# backplane_v3.net
KiCad netlist of a schematic drawn in EAGLE
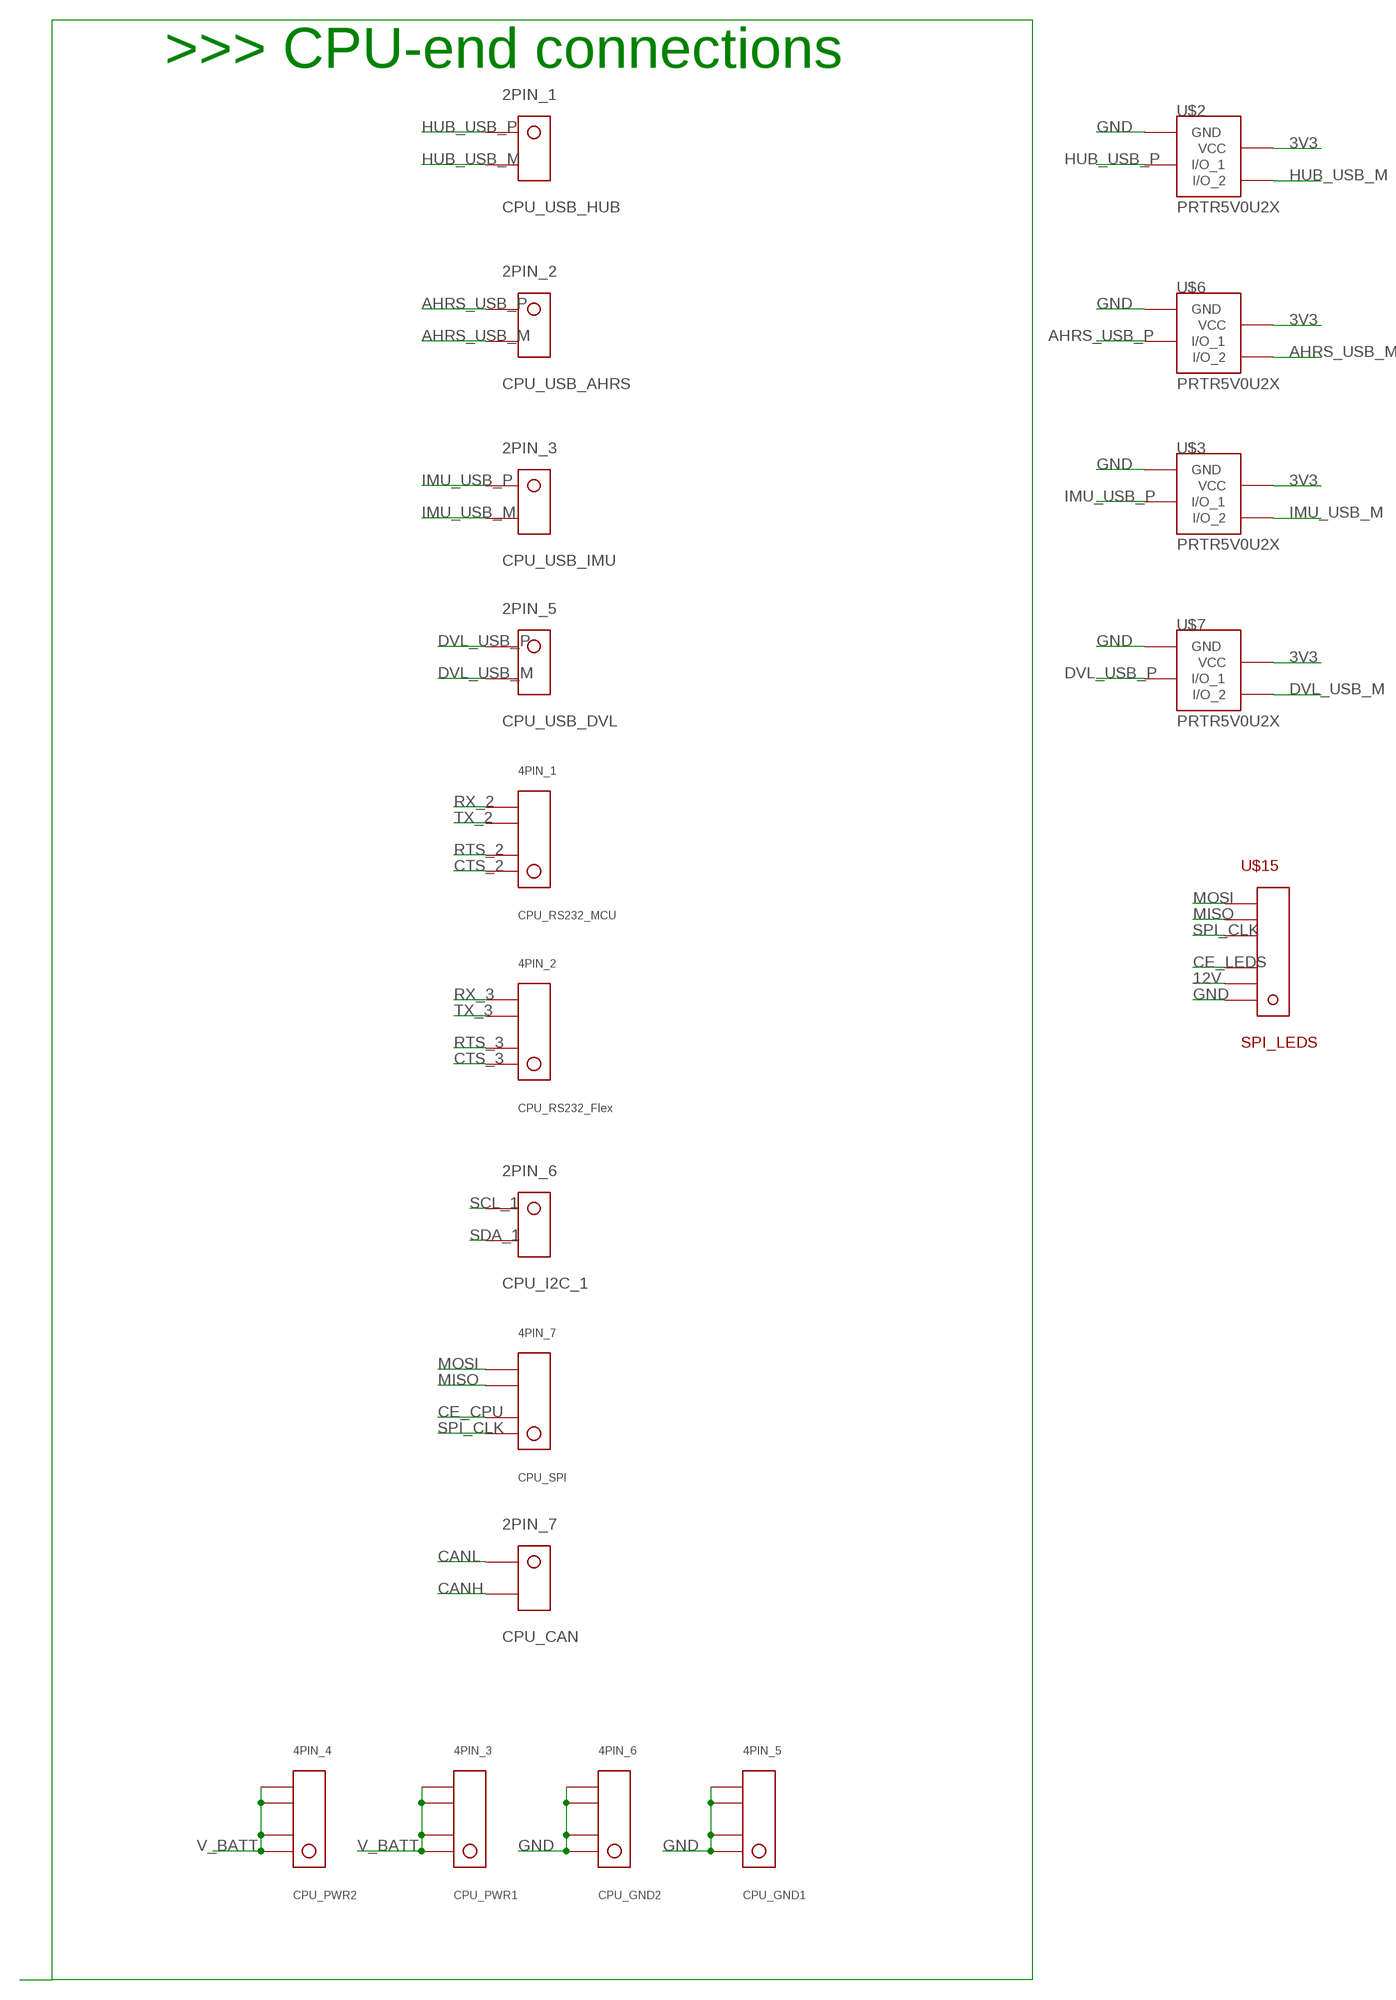
[diagram p0: schematic, sheet 1, part 1 of 3]
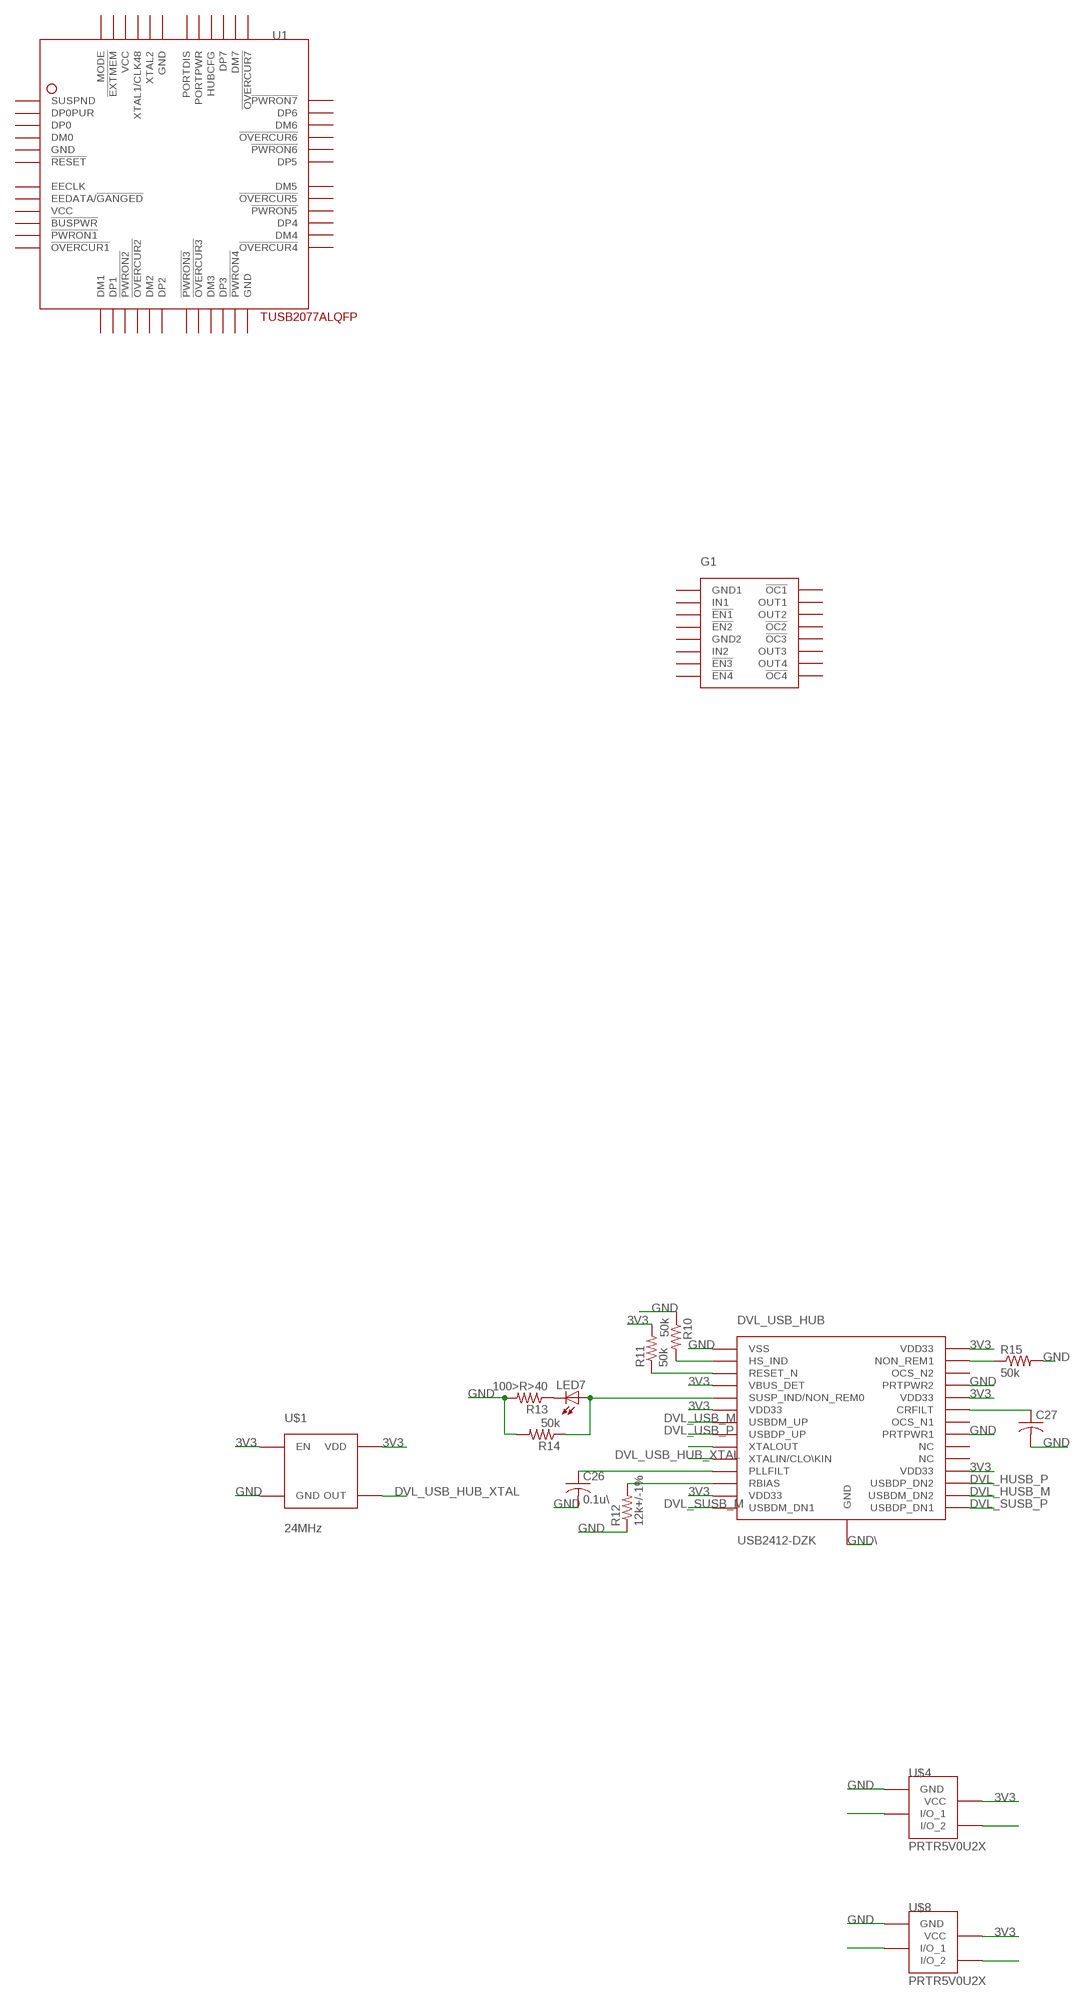
[diagram p1: schematic, sheet 1, part 2 of 3]
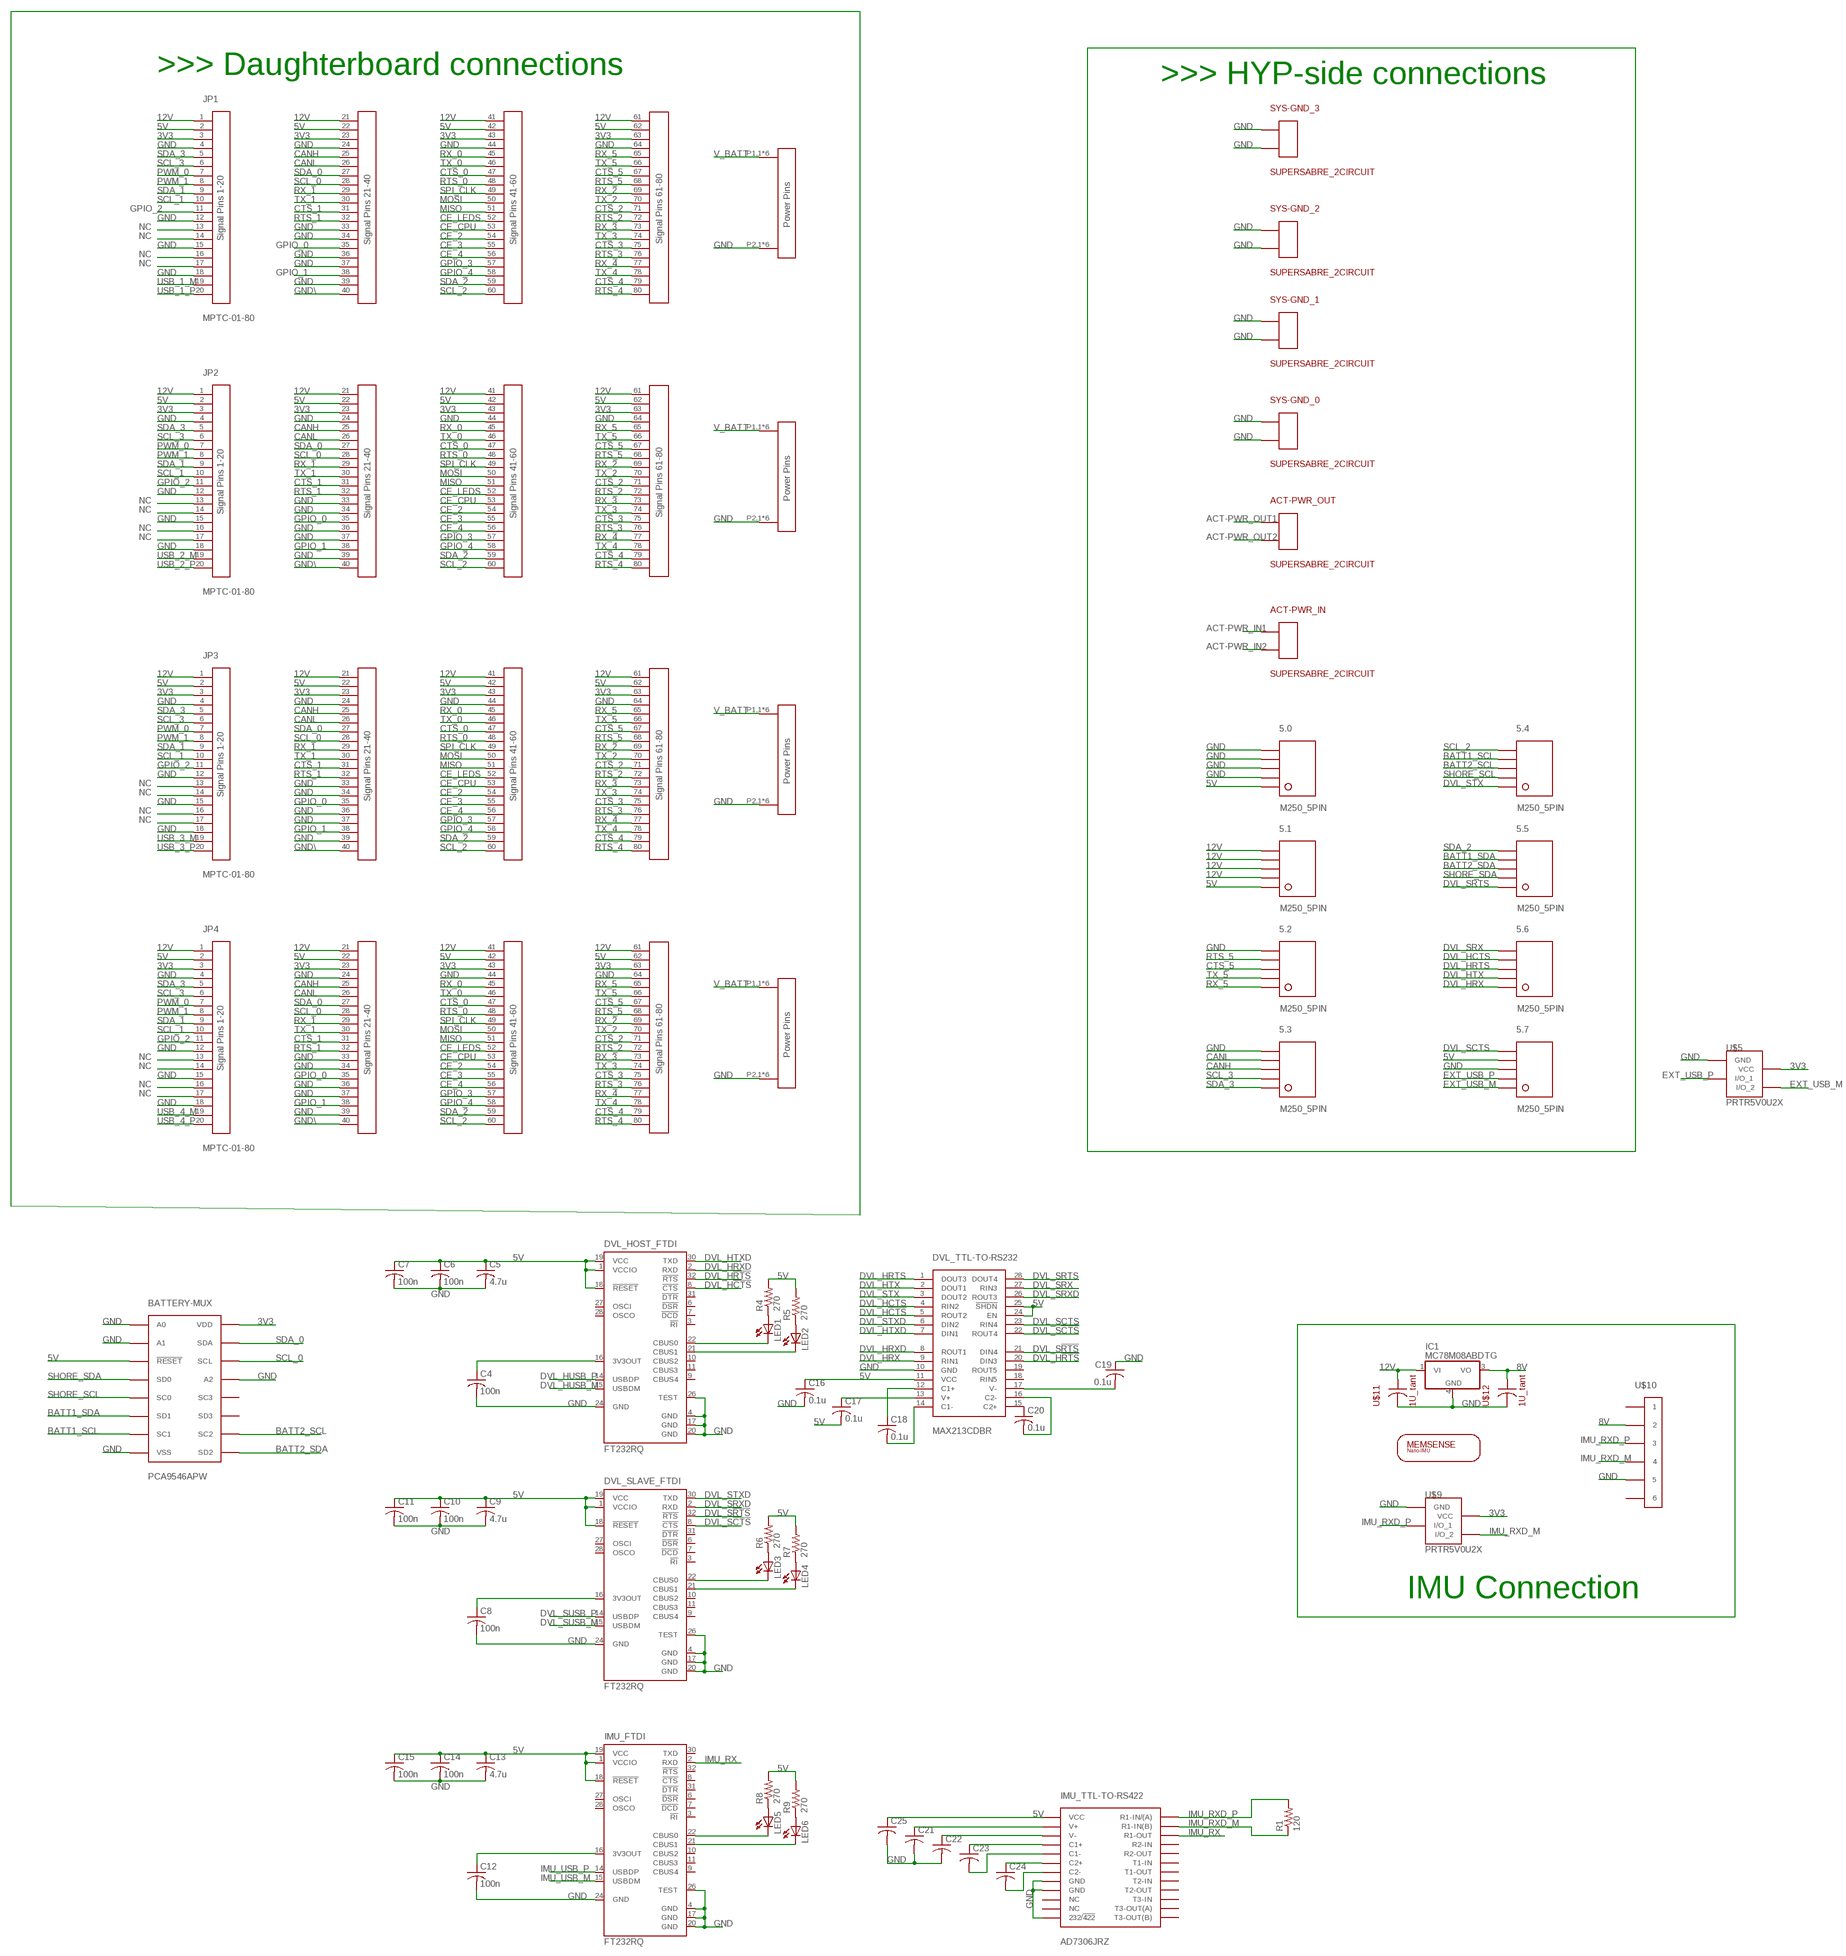
[diagram p2: schematic, sheet 1, part 3 of 3]

(export (version "E")
  (design (tool "Eeschema 10.0.6"))
  (components
    (comp (ref "2PIN_1")
      (value "CPU_USB_HUB")
      (footprint "eagle-import:KK254_VERT_2PIN")
      (libsource (lib "eagle-import") (part "KK254_VERT_2PIN22-29-2021"))
    )
    (comp (ref "2PIN_2")
      (value "CPU_USB_AHRS")
      (footprint "eagle-import:KK254_VERT_2PIN")
      (libsource (lib "eagle-import") (part "KK254_VERT_2PIN22-29-2021"))
    )
    (comp (ref "2PIN_3")
      (value "CPU_USB_IMU")
      (footprint "eagle-import:KK254_VERT_2PIN")
      (libsource (lib "eagle-import") (part "KK254_VERT_2PIN22-29-2021"))
    )
    (comp (ref "2PIN_5")
      (value "CPU_USB_DVL")
      (footprint "eagle-import:KK254_VERT_2PIN")
      (libsource (lib "eagle-import") (part "KK254_VERT_2PIN22-29-2021"))
    )
    (comp (ref "2PIN_6")
      (value "CPU_I2C_1")
      (footprint "eagle-import:KK254_VERT_2PIN")
      (libsource (lib "eagle-import") (part "KK254_VERT_2PIN22-29-2021"))
    )
    (comp (ref "2PIN_7")
      (value "CPU_CAN")
      (footprint "eagle-import:KK254_VERT_2PIN")
      (libsource (lib "eagle-import") (part "KK254_VERT_2PIN22-29-2021"))
    )
    (comp (ref "4PIN_1")
      (value "CPU_RS232_MCU")
      (footprint "eagle-import:KK254_VERT_4PIN")
      (libsource (lib "eagle-import") (part "KK254_VERT_4PIN22-29-2041"))
    )
    (comp (ref "4PIN_2")
      (value "CPU_RS232_Flex")
      (footprint "eagle-import:KK254_VERT_4PIN")
      (libsource (lib "eagle-import") (part "KK254_VERT_4PIN22-29-2041"))
    )
    (comp (ref "4PIN_3")
      (value "CPU_PWR1")
      (footprint "eagle-import:KK254_VERT_4PIN")
      (libsource (lib "eagle-import") (part "KK254_VERT_4PIN22-29-2041"))
    )
    (comp (ref "4PIN_4")
      (value "CPU_PWR2")
      (footprint "eagle-import:KK254_VERT_4PIN")
      (libsource (lib "eagle-import") (part "KK254_VERT_4PIN22-29-2041"))
    )
    (comp (ref "4PIN_5")
      (value "CPU_GND1")
      (footprint "eagle-import:KK254_VERT_4PIN")
      (libsource (lib "eagle-import") (part "KK254_VERT_4PIN22-29-2041"))
    )
    (comp (ref "4PIN_6")
      (value "CPU_GND2")
      (footprint "eagle-import:KK254_VERT_4PIN")
      (libsource (lib "eagle-import") (part "KK254_VERT_4PIN22-29-2041"))
    )
    (comp (ref "4PIN_7")
      (value "CPU_SPI")
      (footprint "eagle-import:KK254_VERT_4PIN")
      (libsource (lib "eagle-import") (part "KK254_VERT_4PIN22-29-2041"))
    )
    (comp (ref "5.0")
      (value "M250_5PIN")
      (footprint "eagle-import:M205_5PIN")
      (libsource (lib "eagle-import") (part "M250_5PIN"))
    )
    (comp (ref "5.1")
      (value "M250_5PIN")
      (footprint "eagle-import:M205_5PIN")
      (libsource (lib "eagle-import") (part "M250_5PIN"))
    )
    (comp (ref "5.2")
      (value "M250_5PIN")
      (footprint "eagle-import:M205_5PIN")
      (libsource (lib "eagle-import") (part "M250_5PIN"))
    )
    (comp (ref "5.3")
      (value "M250_5PIN")
      (footprint "eagle-import:M205_5PIN")
      (libsource (lib "eagle-import") (part "M250_5PIN"))
    )
    (comp (ref "5.4")
      (value "M250_5PIN")
      (footprint "eagle-import:M205_5PIN")
      (libsource (lib "eagle-import") (part "M250_5PIN"))
    )
    (comp (ref "5.5")
      (value "M250_5PIN")
      (footprint "eagle-import:M205_5PIN")
      (libsource (lib "eagle-import") (part "M250_5PIN"))
    )
    (comp (ref "5.6")
      (value "M250_5PIN")
      (footprint "eagle-import:M205_5PIN")
      (libsource (lib "eagle-import") (part "M250_5PIN"))
    )
    (comp (ref "5.7")
      (value "M250_5PIN")
      (footprint "eagle-import:M205_5PIN")
      (libsource (lib "eagle-import") (part "M250_5PIN"))
    )
    (comp (ref "ACT-PWR_IN")
      (value "SUPERSABRE_2CIRCUIT")
      (footprint "eagle-import:SUPERSABRE_2CIRCUIT")
      (libsource (lib "eagle-import") (part "SUPERSABRE_2CIRCUIT"))
    )
    (comp (ref "ACT-PWR_OUT")
      (value "SUPERSABRE_2CIRCUIT")
      (footprint "eagle-import:SUPERSABRE_2CIRCUIT")
      (libsource (lib "eagle-import") (part "SUPERSABRE_2CIRCUIT"))
    )
    (comp (ref "BATTERY-MUX")
      (value "PCA9546APW")
      (footprint "eagle-import:TSSOP16")
      (libsource (lib "eagle-import") (part "PCA9546APW"))
    )
    (comp (ref "C4")
      (value "100n")
      (footprint "eagle-import:C0805")
      (libsource (lib "eagle-import") (part "C-USC0805"))
    )
    (comp (ref "C5")
      (value "4.7u")
      (footprint "eagle-import:C0805")
      (libsource (lib "eagle-import") (part "C-USC0805"))
    )
    (comp (ref "C6")
      (value "100n")
      (footprint "eagle-import:C0805")
      (libsource (lib "eagle-import") (part "C-USC0805"))
    )
    (comp (ref "C7")
      (value "100n")
      (footprint "eagle-import:C0805")
      (libsource (lib "eagle-import") (part "C-USC0805"))
    )
    (comp (ref "C8")
      (value "100n")
      (footprint "eagle-import:C0805")
      (libsource (lib "eagle-import") (part "C-USC0805"))
    )
    (comp (ref "C9")
      (value "4.7u")
      (footprint "eagle-import:C0805")
      (libsource (lib "eagle-import") (part "C-USC0805"))
    )
    (comp (ref "C10")
      (value "100n")
      (footprint "eagle-import:C0805")
      (libsource (lib "eagle-import") (part "C-USC0805"))
    )
    (comp (ref "C11")
      (value "100n")
      (footprint "eagle-import:C0805")
      (libsource (lib "eagle-import") (part "C-USC0805"))
    )
    (comp (ref "C12")
      (value "100n")
      (footprint "eagle-import:C0805")
      (libsource (lib "eagle-import") (part "C-USC0805"))
    )
    (comp (ref "C13")
      (value "4.7u")
      (footprint "eagle-import:C0805")
      (libsource (lib "eagle-import") (part "C-USC0805"))
    )
    (comp (ref "C14")
      (value "100n")
      (footprint "eagle-import:C0805")
      (libsource (lib "eagle-import") (part "C-USC0805"))
    )
    (comp (ref "C15")
      (value "100n")
      (footprint "eagle-import:C0805")
      (libsource (lib "eagle-import") (part "C-USC0805"))
    )
    (comp (ref "C16")
      (value "0.1u")
      (footprint "eagle-import:C0805")
      (libsource (lib "eagle-import") (part "C-USC0805"))
    )
    (comp (ref "C17")
      (value "0.1u")
      (footprint "eagle-import:C0805")
      (libsource (lib "eagle-import") (part "C-USC0805"))
    )
    (comp (ref "C18")
      (value "0.1u")
      (footprint "eagle-import:C0805")
      (libsource (lib "eagle-import") (part "C-USC0805"))
    )
    (comp (ref "C19")
      (value "0.1u")
      (footprint "eagle-import:C0805")
      (libsource (lib "eagle-import") (part "C-USC0805"))
    )
    (comp (ref "C20")
      (value "0.1u")
      (footprint "eagle-import:C0805")
      (libsource (lib "eagle-import") (part "C-USC0805"))
    )
    (comp (ref "C21")
      (value "C-USC0805")
      (footprint "eagle-import:C0805")
      (libsource (lib "eagle-import") (part "C-USC0805"))
    )
    (comp (ref "C22")
      (value "C-USC0805")
      (footprint "eagle-import:C0805")
      (libsource (lib "eagle-import") (part "C-USC0805"))
    )
    (comp (ref "C23")
      (value "C-USC0805")
      (footprint "eagle-import:C0805")
      (libsource (lib "eagle-import") (part "C-USC0805"))
    )
    (comp (ref "C24")
      (value "C-USC0805")
      (footprint "eagle-import:C0805")
      (libsource (lib "eagle-import") (part "C-USC0805"))
    )
    (comp (ref "C25")
      (value "C-USC0805")
      (footprint "eagle-import:C0805")
      (libsource (lib "eagle-import") (part "C-USC0805"))
    )
    (comp (ref "C26")
      (value "0.1u\\")
      (footprint "eagle-import:C0805")
      (libsource (lib "eagle-import") (part "C-USC0805"))
    )
    (comp (ref "C27")
      (value "C-USC0805")
      (footprint "eagle-import:C0805")
      (libsource (lib "eagle-import") (part "C-USC0805"))
    )
    (comp (ref "DVL_HOST_FTDI")
      (value "FT232RQ")
      (footprint "eagle-import:QFN32")
      (libsource (lib "eagle-import") (part "FT232RQ"))
    )
    (comp (ref "DVL_SLAVE_FTDI")
      (value "FT232RQ")
      (footprint "eagle-import:QFN32")
      (libsource (lib "eagle-import") (part "FT232RQ"))
    )
    (comp (ref "DVL_TTL-TO-RS232")
      (value "MAX213CDBR")
      (footprint "eagle-import:SSOP28DB")
      (libsource (lib "eagle-import") (part "MAX213CDBR"))
    )
    (comp (ref "DVL_USB_HUB")
      (value "USB2412-DZK")
      (footprint "eagle-import:QFN-28")
      (libsource (lib "eagle-import") (part "USB2412-DZK"))
    )
    (comp (ref "G1")
      (value "TPS2044BBD-SOIC")
      (footprint "eagle-import:TPS2044")
      (libsource (lib "eagle-import") (part "TPS2044BBD-SOIC"))
    )
    (comp (ref "IC1")
      (value "MC78M08ABDTG")
      (footprint "eagle-import:DPACK_3")
      (libsource (lib "eagle-import") (part "MC78M08ABDTG"))
    )
    (comp (ref "IMU_FTDI")
      (value "FT232RQ")
      (footprint "eagle-import:QFN32")
      (libsource (lib "eagle-import") (part "FT232RQ"))
    )
    (comp (ref "IMU_TTL-TO-RS422")
      (value "AD7306JRZ")
      (footprint "eagle-import:SOIC-24")
      (libsource (lib "eagle-import") (part "AD7306JRZ"))
    )
    (comp (ref "JP1")
      (value "MPTC-01-80")
      (footprint "eagle-import:MPTC-01-80")
      (libsource (lib "eagle-import") (part "MPTC-01-80"))
    )
    (comp (ref "JP2")
      (value "MPTC-01-80")
      (footprint "eagle-import:MPTC-01-80")
      (libsource (lib "eagle-import") (part "MPTC-01-80"))
    )
    (comp (ref "JP3")
      (value "MPTC-01-80")
      (footprint "eagle-import:MPTC-01-80")
      (libsource (lib "eagle-import") (part "MPTC-01-80"))
    )
    (comp (ref "JP4")
      (value "MPTC-01-80")
      (footprint "eagle-import:MPTC-01-80")
      (libsource (lib "eagle-import") (part "MPTC-01-80"))
    )
    (comp (ref "LED1")
      (value "LEDCHIPLED_0805")
      (footprint "eagle-import:CHIPLED_0805")
      (libsource (lib "eagle-import") (part "LEDCHIPLED_0805"))
    )
    (comp (ref "LED2")
      (value "LEDCHIPLED_0805")
      (footprint "eagle-import:CHIPLED_0805")
      (libsource (lib "eagle-import") (part "LEDCHIPLED_0805"))
    )
    (comp (ref "LED3")
      (value "LEDCHIPLED_0805")
      (footprint "eagle-import:CHIPLED_0805")
      (libsource (lib "eagle-import") (part "LEDCHIPLED_0805"))
    )
    (comp (ref "LED4")
      (value "LEDCHIPLED_0805")
      (footprint "eagle-import:CHIPLED_0805")
      (libsource (lib "eagle-import") (part "LEDCHIPLED_0805"))
    )
    (comp (ref "LED5")
      (value "LEDCHIPLED_0805")
      (footprint "eagle-import:CHIPLED_0805")
      (libsource (lib "eagle-import") (part "LEDCHIPLED_0805"))
    )
    (comp (ref "LED6")
      (value "LEDCHIPLED_0805")
      (footprint "eagle-import:CHIPLED_0805")
      (libsource (lib "eagle-import") (part "LEDCHIPLED_0805"))
    )
    (comp (ref "LED7")
      (value "LEDCHIPLED_0805")
      (footprint "eagle-import:CHIPLED_0805")
      (libsource (lib "eagle-import") (part "LEDCHIPLED_0805"))
    )
    (comp (ref "R1")
      (value "120")
      (footprint "eagle-import:R0805")
      (libsource (lib "eagle-import") (part "R-US_R0805"))
    )
    (comp (ref "R4")
      (value "270")
      (footprint "eagle-import:R0805")
      (libsource (lib "eagle-import") (part "R-US_R0805"))
    )
    (comp (ref "R5")
      (value "270")
      (footprint "eagle-import:R0805")
      (libsource (lib "eagle-import") (part "R-US_R0805"))
    )
    (comp (ref "R6")
      (value "270")
      (footprint "eagle-import:R0805")
      (libsource (lib "eagle-import") (part "R-US_R0805"))
    )
    (comp (ref "R7")
      (value "270")
      (footprint "eagle-import:R0805")
      (libsource (lib "eagle-import") (part "R-US_R0805"))
    )
    (comp (ref "R8")
      (value "270")
      (footprint "eagle-import:R0805")
      (libsource (lib "eagle-import") (part "R-US_R0805"))
    )
    (comp (ref "R9")
      (value "270")
      (footprint "eagle-import:R0805")
      (libsource (lib "eagle-import") (part "R-US_R0805"))
    )
    (comp (ref "R10")
      (value "50k")
      (footprint "eagle-import:R0805")
      (libsource (lib "eagle-import") (part "R-US_R0805"))
    )
    (comp (ref "R11")
      (value "50k")
      (footprint "eagle-import:R0805")
      (libsource (lib "eagle-import") (part "R-US_R0805"))
    )
    (comp (ref "R12")
      (value "12k+/-1%")
      (footprint "eagle-import:R0805")
      (libsource (lib "eagle-import") (part "R-US_R0805"))
    )
    (comp (ref "R13")
      (value "100>R>40")
      (footprint "eagle-import:R0805")
      (libsource (lib "eagle-import") (part "R-US_R0805"))
    )
    (comp (ref "R14")
      (value "50k")
      (footprint "eagle-import:R0805")
      (libsource (lib "eagle-import") (part "R-US_R0805"))
    )
    (comp (ref "R15")
      (value "50k")
      (footprint "eagle-import:R0805")
      (libsource (lib "eagle-import") (part "R-US_R0805"))
    )
    (comp (ref "SYS-GND_0")
      (value "SUPERSABRE_2CIRCUIT")
      (footprint "eagle-import:SUPERSABRE_2CIRCUIT")
      (libsource (lib "eagle-import") (part "SUPERSABRE_2CIRCUIT"))
    )
    (comp (ref "SYS-GND_1")
      (value "SUPERSABRE_2CIRCUIT")
      (footprint "eagle-import:SUPERSABRE_2CIRCUIT")
      (libsource (lib "eagle-import") (part "SUPERSABRE_2CIRCUIT"))
    )
    (comp (ref "SYS-GND_2")
      (value "SUPERSABRE_2CIRCUIT")
      (footprint "eagle-import:SUPERSABRE_2CIRCUIT")
      (libsource (lib "eagle-import") (part "SUPERSABRE_2CIRCUIT"))
    )
    (comp (ref "SYS-GND_3")
      (value "SUPERSABRE_2CIRCUIT")
      (footprint "eagle-import:SUPERSABRE_2CIRCUIT")
      (libsource (lib "eagle-import") (part "SUPERSABRE_2CIRCUIT"))
    )
    (comp (ref "U$1")
      (value "24MHz")
      (footprint "eagle-import:4-CDFN_3.2X2.5MM")
      (libsource (lib "eagle-import") (part "DCS6XXX"))
    )
    (comp (ref "U$2")
      (value "PRTR5V0U2X")
      (footprint "eagle-import:SOT143B")
      (libsource (lib "eagle-import") (part "PRTR5V0U2X"))
    )
    (comp (ref "U$3")
      (value "PRTR5V0U2X")
      (footprint "eagle-import:SOT143B")
      (libsource (lib "eagle-import") (part "PRTR5V0U2X"))
    )
    (comp (ref "U$4")
      (value "PRTR5V0U2X")
      (footprint "eagle-import:SOT143B")
      (libsource (lib "eagle-import") (part "PRTR5V0U2X"))
    )
    (comp (ref "U$5")
      (value "PRTR5V0U2X")
      (footprint "eagle-import:SOT143B")
      (libsource (lib "eagle-import") (part "PRTR5V0U2X"))
    )
    (comp (ref "U$6")
      (value "PRTR5V0U2X")
      (footprint "eagle-import:SOT143B")
      (libsource (lib "eagle-import") (part "PRTR5V0U2X"))
    )
    (comp (ref "U$7")
      (value "PRTR5V0U2X")
      (footprint "eagle-import:SOT143B")
      (libsource (lib "eagle-import") (part "PRTR5V0U2X"))
    )
    (comp (ref "U$8")
      (value "PRTR5V0U2X")
      (footprint "eagle-import:SOT143B")
      (libsource (lib "eagle-import") (part "PRTR5V0U2X"))
    )
    (comp (ref "U$9")
      (value "PRTR5V0U2X")
      (footprint "eagle-import:SOT143B")
      (libsource (lib "eagle-import") (part "PRTR5V0U2X"))
    )
    (comp (ref "U$10")
      (value "HR30-6R-6PD")
      (footprint "eagle-import:HR30-6R-6PD")
      (libsource (lib "eagle-import") (part "HR30-6R-6PD"))
    )
    (comp (ref "U$11")
      (value "1U_tant")
      (footprint "eagle-import:F93-XX-XXX-X-A")
      (libsource (lib "eagle-import") (part "F93-XX-XXX-X-A"))
    )
    (comp (ref "U$12")
      (value "1U_tant")
      (footprint "eagle-import:F93-XX-XXX-X-A")
      (libsource (lib "eagle-import") (part "F93-XX-XXX-X-A"))
    )
    (comp (ref "U$13")
      (value "MEMSENSE_NIMU")
      (footprint "eagle-import:MEMSENSE_NIMU")
      (libsource (lib "eagle-import") (part "MEMSENSE_NIMU"))
    )
    (comp (ref "U$15")
      (value "SPI_LEDS")
      (footprint "eagle-import:KK254_6PIN")
      (libsource (lib "eagle-import") (part "KK254_6PIN"))
    )
    (comp (ref "U1")
      (value "TUSB2077ALQFP")
      (footprint "eagle-import:48-LQFP_0.5MM_PITCH")
      (libsource (lib "eagle-import") (part "TUSB2077ALQFP"))
    )
  )
  (nets
    (net (code "1") (name "/3V3") (class "Default")
      (node (ref "BATTERY-MUX") (pin "P$16") (pinfunction "VDD_P$16") (pintype "bidirectional"))
      (node (ref "DVL_USB_HUB") (pin "P$10") (pinfunction "VDD33_P$10") (pintype "bidirectional"))
      (node (ref "DVL_USB_HUB") (pin "P$14") (pinfunction "VDD33_P$14") (pintype "bidirectional"))
      (node (ref "DVL_USB_HUB") (pin "P$18") (pinfunction "VBUS_DET_P$18") (pintype "bidirectional"))
      (node (ref "DVL_USB_HUB") (pin "P$20") (pinfunction "VDD33_P$20") (pintype "bidirectional"))
      (node (ref "DVL_USB_HUB") (pin "P$27") (pinfunction "VDD33_P$27") (pintype "bidirectional"))
      (node (ref "DVL_USB_HUB") (pin "P$4") (pinfunction "VDD33_P$4") (pintype "bidirectional"))
      (node (ref "JP1") (pin "23") (pinfunction "P$23_23") (pintype "bidirectional"))
      (node (ref "JP1") (pin "3") (pinfunction "P$3_3") (pintype "bidirectional"))
      (node (ref "JP1") (pin "43") (pinfunction "P$43_43") (pintype "bidirectional"))
      (node (ref "JP1") (pin "63") (pinfunction "P$63_63") (pintype "bidirectional"))
      (node (ref "JP2") (pin "23") (pinfunction "P$23_23") (pintype "bidirectional"))
      (node (ref "JP2") (pin "3") (pinfunction "P$3_3") (pintype "bidirectional"))
      (node (ref "JP2") (pin "43") (pinfunction "P$43_43") (pintype "bidirectional"))
      (node (ref "JP2") (pin "63") (pinfunction "P$63_63") (pintype "bidirectional"))
      (node (ref "JP3") (pin "23") (pinfunction "P$23_23") (pintype "bidirectional"))
      (node (ref "JP3") (pin "3") (pinfunction "P$3_3") (pintype "bidirectional"))
      (node (ref "JP3") (pin "43") (pinfunction "P$43_43") (pintype "bidirectional"))
      (node (ref "JP3") (pin "63") (pinfunction "P$63_63") (pintype "bidirectional"))
      (node (ref "JP4") (pin "23") (pinfunction "P$23_23") (pintype "bidirectional"))
      (node (ref "JP4") (pin "3") (pinfunction "P$3_3") (pintype "bidirectional"))
      (node (ref "JP4") (pin "43") (pinfunction "P$43_43") (pintype "bidirectional"))
      (node (ref "JP4") (pin "63") (pinfunction "P$63_63") (pintype "bidirectional"))
      (node (ref "R11") (pin "2") (pinfunction "2_2") (pintype "passive"))
      (node (ref "U$1") (pin "P$1") (pinfunction "EN_P$1") (pintype "bidirectional"))
      (node (ref "U$1") (pin "P$4") (pinfunction "VDD_P$4") (pintype "bidirectional"))
      (node (ref "U$2") (pin "P$4") (pinfunction "VCC_P$4") (pintype "bidirectional"))
      (node (ref "U$3") (pin "P$4") (pinfunction "VCC_P$4") (pintype "bidirectional"))
      (node (ref "U$4") (pin "P$4") (pinfunction "VCC_P$4") (pintype "bidirectional"))
      (node (ref "U$5") (pin "P$4") (pinfunction "VCC_P$4") (pintype "bidirectional"))
      (node (ref "U$6") (pin "P$4") (pinfunction "VCC_P$4") (pintype "bidirectional"))
      (node (ref "U$7") (pin "P$4") (pinfunction "VCC_P$4") (pintype "bidirectional"))
      (node (ref "U$8") (pin "P$4") (pinfunction "VCC_P$4") (pintype "bidirectional"))
      (node (ref "U$9") (pin "P$4") (pinfunction "VCC_P$4") (pintype "bidirectional"))
    )
    (net (code "2") (name "/5V") (class "Default")
      (node (ref "5.0") (pin "P$1") (pinfunction "P$1_P$1") (pintype "bidirectional"))
      (node (ref "5.0") (pin "P$2") (pinfunction "P$1_P$2") (pintype "bidirectional"))
      (node (ref "5.1") (pin "P$1") (pinfunction "P$1_P$1") (pintype "bidirectional"))
      (node (ref "5.1") (pin "P$2") (pinfunction "P$1_P$2") (pintype "bidirectional"))
      (node (ref "5.7") (pin "P$7") (pinfunction "P$4_P$7") (pintype "bidirectional"))
      (node (ref "5.7") (pin "P$8") (pinfunction "P$4_P$8") (pintype "bidirectional"))
      (node (ref "BATTERY-MUX") (pin "P$3") (pinfunction "~{RESET}_P$3") (pintype "bidirectional"))
      (node (ref "C10") (pin "1") (pinfunction "1_1") (pintype "passive"))
      (node (ref "C11") (pin "1") (pinfunction "1_1") (pintype "passive"))
      (node (ref "C13") (pin "1") (pinfunction "1_1") (pintype "passive"))
      (node (ref "C14") (pin "1") (pinfunction "1_1") (pintype "passive"))
      (node (ref "C15") (pin "1") (pinfunction "1_1") (pintype "passive"))
      (node (ref "C16") (pin "1") (pinfunction "1_1") (pintype "passive"))
      (node (ref "C17") (pin "2") (pinfunction "2_2") (pintype "passive"))
      (node (ref "C25") (pin "1") (pinfunction "1_1") (pintype "passive"))
      (node (ref "C5") (pin "1") (pinfunction "1_1") (pintype "passive"))
      (node (ref "C6") (pin "1") (pinfunction "1_1") (pintype "passive"))
      (node (ref "C7") (pin "1") (pinfunction "1_1") (pintype "passive"))
      (node (ref "C9") (pin "1") (pinfunction "1_1") (pintype "passive"))
      (node (ref "DVL_HOST_FTDI") (pin "1") (pinfunction "VCCIO_1") (pintype "power_in"))
      (node (ref "DVL_HOST_FTDI") (pin "18") (pinfunction "~{RESET}_18") (pintype "input"))
      (node (ref "DVL_HOST_FTDI") (pin "19") (pinfunction "VCC_19") (pintype "power_in"))
      (node (ref "DVL_SLAVE_FTDI") (pin "1") (pinfunction "VCCIO_1") (pintype "power_in"))
      (node (ref "DVL_SLAVE_FTDI") (pin "18") (pinfunction "~{RESET}_18") (pintype "input"))
      (node (ref "DVL_SLAVE_FTDI") (pin "19") (pinfunction "VCC_19") (pintype "power_in"))
      (node (ref "DVL_TTL-TO-RS232") (pin "11") (pinfunction "VCC_11") (pintype "bidirectional"))
      (node (ref "DVL_TTL-TO-RS232") (pin "24") (pinfunction "EN_24") (pintype "bidirectional"))
      (node (ref "DVL_TTL-TO-RS232") (pin "25") (pinfunction "~{SHDN}_25") (pintype "bidirectional"))
      (node (ref "IMU_FTDI") (pin "1") (pinfunction "VCCIO_1") (pintype "power_in"))
      (node (ref "IMU_FTDI") (pin "18") (pinfunction "~{RESET}_18") (pintype "input"))
      (node (ref "IMU_FTDI") (pin "19") (pinfunction "VCC_19") (pintype "power_in"))
      (node (ref "IMU_TTL-TO-RS422") (pin "P$7") (pinfunction "VCC_P$7") (pintype "bidirectional"))
      (node (ref "JP1") (pin "2") (pinfunction "P$2_2") (pintype "bidirectional"))
      (node (ref "JP1") (pin "22") (pinfunction "P$22_22") (pintype "bidirectional"))
      (node (ref "JP1") (pin "42") (pinfunction "P$42_42") (pintype "bidirectional"))
      (node (ref "JP1") (pin "62") (pinfunction "P$62_62") (pintype "bidirectional"))
      (node (ref "JP2") (pin "2") (pinfunction "P$2_2") (pintype "bidirectional"))
      (node (ref "JP2") (pin "22") (pinfunction "P$22_22") (pintype "bidirectional"))
      (node (ref "JP2") (pin "42") (pinfunction "P$42_42") (pintype "bidirectional"))
      (node (ref "JP2") (pin "62") (pinfunction "P$62_62") (pintype "bidirectional"))
      (node (ref "JP3") (pin "2") (pinfunction "P$2_2") (pintype "bidirectional"))
      (node (ref "JP3") (pin "22") (pinfunction "P$22_22") (pintype "bidirectional"))
      (node (ref "JP3") (pin "42") (pinfunction "P$42_42") (pintype "bidirectional"))
      (node (ref "JP3") (pin "62") (pinfunction "P$62_62") (pintype "bidirectional"))
      (node (ref "JP4") (pin "2") (pinfunction "P$2_2") (pintype "bidirectional"))
      (node (ref "JP4") (pin "22") (pinfunction "P$22_22") (pintype "bidirectional"))
      (node (ref "JP4") (pin "42") (pinfunction "P$42_42") (pintype "bidirectional"))
      (node (ref "JP4") (pin "62") (pinfunction "P$62_62") (pintype "bidirectional"))
      (node (ref "R4") (pin "2") (pinfunction "2_2") (pintype "passive"))
      (node (ref "R5") (pin "2") (pinfunction "2_2") (pintype "passive"))
      (node (ref "R6") (pin "2") (pinfunction "2_2") (pintype "passive"))
      (node (ref "R7") (pin "2") (pinfunction "2_2") (pintype "passive"))
      (node (ref "R8") (pin "2") (pinfunction "2_2") (pintype "passive"))
      (node (ref "R9") (pin "2") (pinfunction "2_2") (pintype "passive"))
    )
    (net (code "3") (name "/8V") (class "Default")
      (node (ref "IC1") (pin "3") (pinfunction "VO_3") (pintype "passive"))
      (node (ref "U$10") (pin "P$2") (pinfunction "2_P$2") (pintype "bidirectional"))
      (node (ref "U$12") (pin "P$1") (pinfunction "+_P$1") (pintype "bidirectional"))
    )
    (net (code "4") (name "/12V") (class "Default")
      (node (ref "5.1") (pin "P$10") (pinfunction "P$5_P$10") (pintype "bidirectional"))
      (node (ref "5.1") (pin "P$3") (pinfunction "P$2_P$3") (pintype "bidirectional"))
      (node (ref "5.1") (pin "P$4") (pinfunction "P$2_P$4") (pintype "bidirectional"))
      (node (ref "5.1") (pin "P$5") (pinfunction "P$3_P$5") (pintype "bidirectional"))
      (node (ref "5.1") (pin "P$6") (pinfunction "P$3_P$6") (pintype "bidirectional"))
      (node (ref "5.1") (pin "P$7") (pinfunction "P$4_P$7") (pintype "bidirectional"))
      (node (ref "5.1") (pin "P$8") (pinfunction "P$4_P$8") (pintype "bidirectional"))
      (node (ref "5.1") (pin "P$9") (pinfunction "P$5_P$9") (pintype "bidirectional"))
      (node (ref "IC1") (pin "1") (pinfunction "VI_1") (pintype "input"))
      (node (ref "JP1") (pin "1") (pinfunction "P$1_1") (pintype "bidirectional"))
      (node (ref "JP1") (pin "21") (pinfunction "P$21_21") (pintype "bidirectional"))
      (node (ref "JP1") (pin "41") (pinfunction "P$41_41") (pintype "bidirectional"))
      (node (ref "JP1") (pin "61") (pinfunction "P$61_61") (pintype "bidirectional"))
      (node (ref "JP2") (pin "1") (pinfunction "P$1_1") (pintype "bidirectional"))
      (node (ref "JP2") (pin "21") (pinfunction "P$21_21") (pintype "bidirectional"))
      (node (ref "JP2") (pin "41") (pinfunction "P$41_41") (pintype "bidirectional"))
      (node (ref "JP2") (pin "61") (pinfunction "P$61_61") (pintype "bidirectional"))
      (node (ref "JP3") (pin "1") (pinfunction "P$1_1") (pintype "bidirectional"))
      (node (ref "JP3") (pin "21") (pinfunction "P$21_21") (pintype "bidirectional"))
      (node (ref "JP3") (pin "41") (pinfunction "P$41_41") (pintype "bidirectional"))
      (node (ref "JP3") (pin "61") (pinfunction "P$61_61") (pintype "bidirectional"))
      (node (ref "JP4") (pin "1") (pinfunction "P$1_1") (pintype "bidirectional"))
      (node (ref "JP4") (pin "21") (pinfunction "P$21_21") (pintype "bidirectional"))
      (node (ref "JP4") (pin "41") (pinfunction "P$41_41") (pintype "bidirectional"))
      (node (ref "JP4") (pin "61") (pinfunction "P$61_61") (pintype "bidirectional"))
      (node (ref "U$11") (pin "P$1") (pinfunction "+_P$1") (pintype "bidirectional"))
      (node (ref "U$15") (pin "P$2") (pinfunction "P$2_P$2") (pintype "bidirectional"))
    )
    (net (code "5") (name "/ACT-PWR_IN1") (class "Default")
      (node (ref "ACT-PWR_IN") (pin "P$1") (pinfunction "P$1_P$1") (pintype "bidirectional"))
    )
    (net (code "6") (name "/ACT-PWR_IN2") (class "Default")
      (node (ref "ACT-PWR_IN") (pin "P$2") (pinfunction "P$2_P$2") (pintype "bidirectional"))
    )
    (net (code "7") (name "/ACT-PWR_OUT1") (class "Default")
      (node (ref "ACT-PWR_OUT") (pin "P$1") (pinfunction "P$1_P$1") (pintype "bidirectional"))
    )
    (net (code "8") (name "/ACT-PWR_OUT2") (class "Default")
      (node (ref "ACT-PWR_OUT") (pin "P$2") (pinfunction "P$2_P$2") (pintype "bidirectional"))
    )
    (net (code "9") (name "/AHRS_USB_M") (class "Default")
      (node (ref "2PIN_2") (pin "P$2") (pinfunction "P$2_P$2") (pintype "bidirectional"))
      (node (ref "U$6") (pin "P$3") (pinfunction "I/O_2_P$3") (pintype "bidirectional"))
    )
    (net (code "10") (name "/AHRS_USB_P") (class "Default")
      (node (ref "2PIN_2") (pin "P$1") (pinfunction "P$1_P$1") (pintype "bidirectional"))
      (node (ref "U$6") (pin "P$2") (pinfunction "I/O_1_P$2") (pintype "bidirectional"))
    )
    (net (code "11") (name "/BATT1_SCL") (class "Default")
      (node (ref "5.4") (pin "P$7") (pinfunction "P$4_P$7") (pintype "bidirectional"))
      (node (ref "5.4") (pin "P$8") (pinfunction "P$4_P$8") (pintype "bidirectional"))
      (node (ref "BATTERY-MUX") (pin "P$7") (pinfunction "SC1_P$7") (pintype "bidirectional"))
    )
    (net (code "12") (name "/BATT1_SDA") (class "Default")
      (node (ref "5.5") (pin "P$7") (pinfunction "P$4_P$7") (pintype "bidirectional"))
      (node (ref "5.5") (pin "P$8") (pinfunction "P$4_P$8") (pintype "bidirectional"))
      (node (ref "BATTERY-MUX") (pin "P$6") (pinfunction "SD1_P$6") (pintype "bidirectional"))
    )
    (net (code "13") (name "/BATT2_SCL") (class "Default")
      (node (ref "5.4") (pin "P$5") (pinfunction "P$3_P$5") (pintype "bidirectional"))
      (node (ref "5.4") (pin "P$6") (pinfunction "P$3_P$6") (pintype "bidirectional"))
      (node (ref "BATTERY-MUX") (pin "P$10") (pinfunction "SC2_P$10") (pintype "bidirectional"))
    )
    (net (code "14") (name "/BATT2_SDA") (class "Default")
      (node (ref "5.5") (pin "P$5") (pinfunction "P$3_P$5") (pintype "bidirectional"))
      (node (ref "5.5") (pin "P$6") (pinfunction "P$3_P$6") (pintype "bidirectional"))
      (node (ref "BATTERY-MUX") (pin "P$9") (pinfunction "SD2_P$9") (pintype "bidirectional"))
    )
    (net (code "15") (name "/CANH") (class "Default")
      (node (ref "2PIN_7") (pin "P$2") (pinfunction "P$2_P$2") (pintype "bidirectional"))
      (node (ref "5.3") (pin "P$5") (pinfunction "P$3_P$5") (pintype "bidirectional"))
      (node (ref "5.3") (pin "P$6") (pinfunction "P$3_P$6") (pintype "bidirectional"))
      (node (ref "JP1") (pin "25") (pinfunction "P$25_25") (pintype "bidirectional"))
      (node (ref "JP2") (pin "25") (pinfunction "P$25_25") (pintype "bidirectional"))
      (node (ref "JP3") (pin "25") (pinfunction "P$25_25") (pintype "bidirectional"))
      (node (ref "JP4") (pin "25") (pinfunction "P$25_25") (pintype "bidirectional"))
    )
    (net (code "16") (name "/CANL") (class "Default")
      (node (ref "2PIN_7") (pin "P$1") (pinfunction "P$1_P$1") (pintype "bidirectional"))
      (node (ref "5.3") (pin "P$7") (pinfunction "P$4_P$7") (pintype "bidirectional"))
      (node (ref "5.3") (pin "P$8") (pinfunction "P$4_P$8") (pintype "bidirectional"))
      (node (ref "JP1") (pin "26") (pinfunction "P$26_26") (pintype "bidirectional"))
      (node (ref "JP2") (pin "26") (pinfunction "P$26_26") (pintype "bidirectional"))
      (node (ref "JP3") (pin "26") (pinfunction "P$26_26") (pintype "bidirectional"))
      (node (ref "JP4") (pin "26") (pinfunction "P$26_26") (pintype "bidirectional"))
    )
    (net (code "17") (name "/CE_2") (class "Default")
      (node (ref "JP1") (pin "54") (pinfunction "P$54_54") (pintype "bidirectional"))
      (node (ref "JP2") (pin "54") (pinfunction "P$54_54") (pintype "bidirectional"))
      (node (ref "JP3") (pin "54") (pinfunction "P$54_54") (pintype "bidirectional"))
      (node (ref "JP4") (pin "54") (pinfunction "P$54_54") (pintype "bidirectional"))
    )
    (net (code "18") (name "/CE_3") (class "Default")
      (node (ref "JP1") (pin "55") (pinfunction "P$55_55") (pintype "bidirectional"))
      (node (ref "JP2") (pin "55") (pinfunction "P$55_55") (pintype "bidirectional"))
      (node (ref "JP3") (pin "55") (pinfunction "P$55_55") (pintype "bidirectional"))
      (node (ref "JP4") (pin "55") (pinfunction "P$55_55") (pintype "bidirectional"))
    )
    (net (code "19") (name "/CE_4") (class "Default")
      (node (ref "JP1") (pin "56") (pinfunction "P$56_56") (pintype "bidirectional"))
      (node (ref "JP2") (pin "56") (pinfunction "P$56_56") (pintype "bidirectional"))
      (node (ref "JP3") (pin "56") (pinfunction "P$56_56") (pintype "bidirectional"))
      (node (ref "JP4") (pin "56") (pinfunction "P$56_56") (pintype "bidirectional"))
    )
    (net (code "20") (name "/CE_CPU") (class "Default")
      (node (ref "4PIN_7") (pin "P$2") (pinfunction "P$2_P$2") (pintype "bidirectional"))
      (node (ref "JP1") (pin "53") (pinfunction "P$53_53") (pintype "bidirectional"))
      (node (ref "JP2") (pin "53") (pinfunction "P$53_53") (pintype "bidirectional"))
      (node (ref "JP3") (pin "53") (pinfunction "P$53_53") (pintype "bidirectional"))
      (node (ref "JP4") (pin "53") (pinfunction "P$53_53") (pintype "bidirectional"))
    )
    (net (code "21") (name "/CE_LEDS") (class "Default")
      (node (ref "JP1") (pin "52") (pinfunction "P$52_52") (pintype "bidirectional"))
      (node (ref "JP2") (pin "52") (pinfunction "P$52_52") (pintype "bidirectional"))
      (node (ref "JP3") (pin "52") (pinfunction "P$52_52") (pintype "bidirectional"))
      (node (ref "JP4") (pin "52") (pinfunction "P$52_52") (pintype "bidirectional"))
      (node (ref "U$15") (pin "P$3") (pinfunction "P$3_P$3") (pintype "bidirectional"))
    )
    (net (code "22") (name "/CTS_0") (class "Default")
      (node (ref "JP1") (pin "47") (pinfunction "P$47_47") (pintype "bidirectional"))
      (node (ref "JP2") (pin "47") (pinfunction "P$47_47") (pintype "bidirectional"))
      (node (ref "JP3") (pin "47") (pinfunction "P$47_47") (pintype "bidirectional"))
      (node (ref "JP4") (pin "47") (pinfunction "P$47_47") (pintype "bidirectional"))
    )
    (net (code "23") (name "/CTS_1") (class "Default")
      (node (ref "JP1") (pin "31") (pinfunction "P$31_31") (pintype "bidirectional"))
      (node (ref "JP2") (pin "31") (pinfunction "P$31_31") (pintype "bidirectional"))
      (node (ref "JP3") (pin "31") (pinfunction "P$31_31") (pintype "bidirectional"))
      (node (ref "JP4") (pin "31") (pinfunction "P$31_31") (pintype "bidirectional"))
    )
    (net (code "24") (name "/CTS_2") (class "Default")
      (node (ref "4PIN_1") (pin "P$1") (pinfunction "P$1_P$1") (pintype "bidirectional"))
      (node (ref "JP1") (pin "71") (pinfunction "P$71_71") (pintype "bidirectional"))
      (node (ref "JP2") (pin "71") (pinfunction "P$71_71") (pintype "bidirectional"))
      (node (ref "JP3") (pin "71") (pinfunction "P$71_71") (pintype "bidirectional"))
      (node (ref "JP4") (pin "71") (pinfunction "P$71_71") (pintype "bidirectional"))
    )
    (net (code "25") (name "/CTS_3") (class "Default")
      (node (ref "4PIN_2") (pin "P$1") (pinfunction "P$1_P$1") (pintype "bidirectional"))
      (node (ref "JP1") (pin "75") (pinfunction "P$75_75") (pintype "bidirectional"))
      (node (ref "JP2") (pin "75") (pinfunction "P$75_75") (pintype "bidirectional"))
      (node (ref "JP3") (pin "75") (pinfunction "P$75_75") (pintype "bidirectional"))
      (node (ref "JP4") (pin "75") (pinfunction "P$75_75") (pintype "bidirectional"))
    )
    (net (code "26") (name "/CTS_4") (class "Default")
      (node (ref "JP1") (pin "79") (pinfunction "P$79_79") (pintype "bidirectional"))
      (node (ref "JP2") (pin "79") (pinfunction "P$79_79") (pintype "bidirectional"))
      (node (ref "JP3") (pin "79") (pinfunction "P$79_79") (pintype "bidirectional"))
      (node (ref "JP4") (pin "79") (pinfunction "P$79_79") (pintype "bidirectional"))
    )
    (net (code "27") (name "/CTS_5") (class "Default")
      (node (ref "5.2") (pin "P$5") (pinfunction "P$3_P$5") (pintype "bidirectional"))
      (node (ref "5.2") (pin "P$6") (pinfunction "P$3_P$6") (pintype "bidirectional"))
      (node (ref "JP1") (pin "67") (pinfunction "P$67_67") (pintype "bidirectional"))
      (node (ref "JP2") (pin "67") (pinfunction "P$67_67") (pintype "bidirectional"))
      (node (ref "JP3") (pin "67") (pinfunction "P$67_67") (pintype "bidirectional"))
      (node (ref "JP4") (pin "67") (pinfunction "P$67_67") (pintype "bidirectional"))
    )
    (net (code "28") (name "/DVL_HCTS") (class "Default")
      (node (ref "5.6") (pin "P$7") (pinfunction "P$4_P$7") (pintype "bidirectional"))
      (node (ref "5.6") (pin "P$8") (pinfunction "P$4_P$8") (pintype "bidirectional"))
      (node (ref "DVL_TTL-TO-RS232") (pin "4") (pinfunction "RIN2_4") (pintype "bidirectional"))
    )
    (net (code "29") (name "/DVL_HRTS") (class "Default")
      (node (ref "5.6") (pin "P$5") (pinfunction "P$3_P$5") (pintype "bidirectional"))
      (node (ref "5.6") (pin "P$6") (pinfunction "P$3_P$6") (pintype "bidirectional"))
      (node (ref "DVL_TTL-TO-RS232") (pin "1") (pinfunction "DOUT3_1") (pintype "bidirectional"))
    )
    (net (code "30") (name "/DVL_HRX") (class "Default")
      (node (ref "5.6") (pin "P$1") (pinfunction "P$1_P$1") (pintype "bidirectional"))
      (node (ref "5.6") (pin "P$2") (pinfunction "P$1_P$2") (pintype "bidirectional"))
      (node (ref "DVL_TTL-TO-RS232") (pin "9") (pinfunction "RIN1_9") (pintype "bidirectional"))
    )
    (net (code "31") (name "/DVL_HRXD") (class "Default")
      (node (ref "DVL_HOST_FTDI") (pin "2") (pinfunction "RXD_2") (pintype "input"))
      (node (ref "DVL_TTL-TO-RS232") (pin "8") (pinfunction "ROUT1_8") (pintype "bidirectional"))
    )
    (net (code "32") (name "/DVL_HTX") (class "Default")
      (node (ref "5.6") (pin "P$3") (pinfunction "P$2_P$3") (pintype "bidirectional"))
      (node (ref "5.6") (pin "P$4") (pinfunction "P$2_P$4") (pintype "bidirectional"))
      (node (ref "DVL_TTL-TO-RS232") (pin "2") (pinfunction "DOUT1_2") (pintype "bidirectional"))
    )
    (net (code "33") (name "/DVL_HTXD") (class "Default")
      (node (ref "DVL_HOST_FTDI") (pin "30") (pinfunction "TXD_30") (pintype "output"))
      (node (ref "DVL_TTL-TO-RS232") (pin "7") (pinfunction "DIN1_7") (pintype "bidirectional"))
    )
    (net (code "34") (name "/DVL_HUSB_M") (class "Default")
      (node (ref "DVL_HOST_FTDI") (pin "15") (pinfunction "USBDM_15") (pintype "bidirectional"))
      (node (ref "DVL_USB_HUB") (pin "P$2") (pinfunction "USBDM_DN2_P$2") (pintype "bidirectional"))
    )
    (net (code "35") (name "/DVL_HUSB_P") (class "Default")
      (node (ref "DVL_HOST_FTDI") (pin "14") (pinfunction "USBDP_14") (pintype "bidirectional"))
      (node (ref "DVL_USB_HUB") (pin "P$3") (pinfunction "USBDP_DN2_P$3") (pintype "bidirectional"))
    )
    (net (code "36") (name "/DVL_H~{CTS}") (class "Default")
      (node (ref "DVL_HOST_FTDI") (pin "8") (pinfunction "~{CTS}_8") (pintype "input"))
      (node (ref "DVL_TTL-TO-RS232") (pin "5") (pinfunction "ROUT2_5") (pintype "bidirectional"))
    )
    (net (code "37") (name "/DVL_H~{RTS}") (class "Default")
      (node (ref "DVL_HOST_FTDI") (pin "32") (pinfunction "~{RTS}_32") (pintype "output"))
      (node (ref "DVL_TTL-TO-RS232") (pin "20") (pinfunction "DIN3_20") (pintype "bidirectional"))
    )
    (net (code "38") (name "/DVL_SCTS") (class "Default")
      (node (ref "5.7") (pin "P$10") (pinfunction "P$5_P$10") (pintype "bidirectional"))
      (node (ref "5.7") (pin "P$9") (pinfunction "P$5_P$9") (pintype "bidirectional"))
      (node (ref "DVL_TTL-TO-RS232") (pin "23") (pinfunction "RIN4_23") (pintype "bidirectional"))
    )
    (net (code "39") (name "/DVL_SRTS") (class "Default")
      (node (ref "5.5") (pin "P$1") (pinfunction "P$1_P$1") (pintype "bidirectional"))
      (node (ref "5.5") (pin "P$2") (pinfunction "P$1_P$2") (pintype "bidirectional"))
      (node (ref "DVL_TTL-TO-RS232") (pin "28") (pinfunction "DOUT4_28") (pintype "bidirectional"))
    )
    (net (code "40") (name "/DVL_SRX") (class "Default")
      (node (ref "5.6") (pin "P$10") (pinfunction "P$5_P$10") (pintype "bidirectional"))
      (node (ref "5.6") (pin "P$9") (pinfunction "P$5_P$9") (pintype "bidirectional"))
      (node (ref "DVL_TTL-TO-RS232") (pin "27") (pinfunction "RIN3_27") (pintype "bidirectional"))
    )
    (net (code "41") (name "/DVL_SRXD") (class "Default")
      (node (ref "DVL_SLAVE_FTDI") (pin "2") (pinfunction "RXD_2") (pintype "input"))
      (node (ref "DVL_TTL-TO-RS232") (pin "26") (pinfunction "ROUT3_26") (pintype "bidirectional"))
    )
    (net (code "42") (name "/DVL_STX") (class "Default")
      (node (ref "5.4") (pin "P$1") (pinfunction "P$1_P$1") (pintype "bidirectional"))
      (node (ref "5.4") (pin "P$2") (pinfunction "P$1_P$2") (pintype "bidirectional"))
      (node (ref "DVL_TTL-TO-RS232") (pin "3") (pinfunction "DOUT2_3") (pintype "bidirectional"))
    )
    (net (code "43") (name "/DVL_STXD") (class "Default")
      (node (ref "DVL_SLAVE_FTDI") (pin "30") (pinfunction "TXD_30") (pintype "output"))
      (node (ref "DVL_TTL-TO-RS232") (pin "6") (pinfunction "DIN2_6") (pintype "bidirectional"))
    )
    (net (code "44") (name "/DVL_SUSB_M") (class "Default")
      (node (ref "DVL_SLAVE_FTDI") (pin "15") (pinfunction "USBDM_15") (pintype "bidirectional"))
      (node (ref "DVL_USB_HUB") (pin "P$28") (pinfunction "USBDM_DN1_P$28") (pintype "bidirectional"))
    )
    (net (code "45") (name "/DVL_SUSB_P") (class "Default")
      (node (ref "DVL_SLAVE_FTDI") (pin "14") (pinfunction "USBDP_14") (pintype "bidirectional"))
      (node (ref "DVL_USB_HUB") (pin "P$1") (pinfunction "USBDP_DN1_P$1") (pintype "bidirectional"))
    )
    (net (code "46") (name "/DVL_S~{CTS}") (class "Default")
      (node (ref "DVL_SLAVE_FTDI") (pin "8") (pinfunction "~{CTS}_8") (pintype "input"))
      (node (ref "DVL_TTL-TO-RS232") (pin "22") (pinfunction "ROUT4_22") (pintype "bidirectional"))
    )
    (net (code "47") (name "/DVL_S~{RTS}") (class "Default")
      (node (ref "DVL_SLAVE_FTDI") (pin "32") (pinfunction "~{RTS}_32") (pintype "output"))
      (node (ref "DVL_TTL-TO-RS232") (pin "21") (pinfunction "DIN4_21") (pintype "bidirectional"))
    )
    (net (code "48") (name "/DVL_USB_HUB_XTAL") (class "Default")
      (node (ref "DVL_USB_HUB") (pin "P$24") (pinfunction "XTALIN/CLO\\KIN_P$24") (pintype "bidirectional"))
      (node (ref "U$1") (pin "P$3") (pinfunction "OUT_P$3") (pintype "bidirectional"))
    )
    (net (code "49") (name "/DVL_USB_M") (class "Default")
      (node (ref "2PIN_5") (pin "P$2") (pinfunction "P$2_P$2") (pintype "bidirectional"))
      (node (ref "DVL_USB_HUB") (pin "P$21") (pinfunction "USBDM_UP_P$21") (pintype "bidirectional"))
      (node (ref "U$7") (pin "P$3") (pinfunction "I/O_2_P$3") (pintype "bidirectional"))
    )
    (net (code "50") (name "/DVL_USB_P") (class "Default")
      (node (ref "2PIN_5") (pin "P$1") (pinfunction "P$1_P$1") (pintype "bidirectional"))
      (node (ref "DVL_USB_HUB") (pin "P$22") (pinfunction "USBDP_UP_P$22") (pintype "bidirectional"))
      (node (ref "U$7") (pin "P$2") (pinfunction "I/O_1_P$2") (pintype "bidirectional"))
    )
    (net (code "51") (name "/EXT_USB_M") (class "Default")
      (node (ref "5.7") (pin "P$1") (pinfunction "P$1_P$1") (pintype "bidirectional"))
      (node (ref "5.7") (pin "P$2") (pinfunction "P$1_P$2") (pintype "bidirectional"))
      (node (ref "U$5") (pin "P$3") (pinfunction "I/O_2_P$3") (pintype "bidirectional"))
    )
    (net (code "52") (name "/EXT_USB_P") (class "Default")
      (node (ref "5.7") (pin "P$3") (pinfunction "P$2_P$3") (pintype "bidirectional"))
      (node (ref "5.7") (pin "P$4") (pinfunction "P$2_P$4") (pintype "bidirectional"))
      (node (ref "U$5") (pin "P$2") (pinfunction "I/O_1_P$2") (pintype "bidirectional"))
    )
    (net (code "53") (name "/GND") (class "Default")
      (node (ref "4PIN_5") (pin "P$1") (pinfunction "P$1_P$1") (pintype "bidirectional"))
      (node (ref "4PIN_5") (pin "P$2") (pinfunction "P$2_P$2") (pintype "bidirectional"))
      (node (ref "4PIN_5") (pin "P$3") (pinfunction "P$3_P$3") (pintype "bidirectional"))
      (node (ref "4PIN_5") (pin "P$4") (pinfunction "P$4_P$4") (pintype "bidirectional"))
      (node (ref "4PIN_6") (pin "P$1") (pinfunction "P$1_P$1") (pintype "bidirectional"))
      (node (ref "4PIN_6") (pin "P$2") (pinfunction "P$2_P$2") (pintype "bidirectional"))
      (node (ref "4PIN_6") (pin "P$3") (pinfunction "P$3_P$3") (pintype "bidirectional"))
      (node (ref "4PIN_6") (pin "P$4") (pinfunction "P$4_P$4") (pintype "bidirectional"))
      (node (ref "5.0") (pin "P$10") (pinfunction "P$5_P$10") (pintype "bidirectional"))
      (node (ref "5.0") (pin "P$3") (pinfunction "P$2_P$3") (pintype "bidirectional"))
      (node (ref "5.0") (pin "P$4") (pinfunction "P$2_P$4") (pintype "bidirectional"))
      (node (ref "5.0") (pin "P$5") (pinfunction "P$3_P$5") (pintype "bidirectional"))
      (node (ref "5.0") (pin "P$6") (pinfunction "P$3_P$6") (pintype "bidirectional"))
      (node (ref "5.0") (pin "P$7") (pinfunction "P$4_P$7") (pintype "bidirectional"))
      (node (ref "5.0") (pin "P$8") (pinfunction "P$4_P$8") (pintype "bidirectional"))
      (node (ref "5.0") (pin "P$9") (pinfunction "P$5_P$9") (pintype "bidirectional"))
      (node (ref "5.2") (pin "P$10") (pinfunction "P$5_P$10") (pintype "bidirectional"))
      (node (ref "5.2") (pin "P$9") (pinfunction "P$5_P$9") (pintype "bidirectional"))
      (node (ref "5.3") (pin "P$10") (pinfunction "P$5_P$10") (pintype "bidirectional"))
      (node (ref "5.3") (pin "P$9") (pinfunction "P$5_P$9") (pintype "bidirectional"))
      (node (ref "5.7") (pin "P$5") (pinfunction "P$3_P$5") (pintype "bidirectional"))
      (node (ref "5.7") (pin "P$6") (pinfunction "P$3_P$6") (pintype "bidirectional"))
      (node (ref "BATTERY-MUX") (pin "P$1") (pinfunction "A0_P$1") (pintype "bidirectional"))
      (node (ref "BATTERY-MUX") (pin "P$13") (pinfunction "A2_P$13") (pintype "bidirectional"))
      (node (ref "BATTERY-MUX") (pin "P$2") (pinfunction "A1_P$2") (pintype "bidirectional"))
      (node (ref "BATTERY-MUX") (pin "P$8") (pinfunction "VSS_P$8") (pintype "bidirectional"))
      (node (ref "C10") (pin "2") (pinfunction "2_2") (pintype "passive"))
      (node (ref "C11") (pin "2") (pinfunction "2_2") (pintype "passive"))
      (node (ref "C12") (pin "2") (pinfunction "2_2") (pintype "passive"))
      (node (ref "C13") (pin "2") (pinfunction "2_2") (pintype "passive"))
      (node (ref "C14") (pin "2") (pinfunction "2_2") (pintype "passive"))
      (node (ref "C15") (pin "2") (pinfunction "2_2") (pintype "passive"))
      (node (ref "C16") (pin "2") (pinfunction "2_2") (pintype "passive"))
      (node (ref "C19") (pin "1") (pinfunction "1_1") (pintype "passive"))
      (node (ref "C21") (pin "2") (pinfunction "2_2") (pintype "passive"))
      (node (ref "C22") (pin "2") (pinfunction "2_2") (pintype "passive"))
      (node (ref "C25") (pin "2") (pinfunction "2_2") (pintype "passive"))
      (node (ref "C26") (pin "2") (pinfunction "2_2") (pintype "passive"))
      (node (ref "C27") (pin "2") (pinfunction "2_2") (pintype "passive"))
      (node (ref "C4") (pin "2") (pinfunction "2_2") (pintype "passive"))
      (node (ref "C5") (pin "2") (pinfunction "2_2") (pintype "passive"))
      (node (ref "C6") (pin "2") (pinfunction "2_2") (pintype "passive"))
      (node (ref "C7") (pin "2") (pinfunction "2_2") (pintype "passive"))
      (node (ref "C8") (pin "2") (pinfunction "2_2") (pintype "passive"))
      (node (ref "C9") (pin "2") (pinfunction "2_2") (pintype "passive"))
      (node (ref "DVL_HOST_FTDI") (pin "17") (pinfunction "GND_17") (pintype "power_in"))
      (node (ref "DVL_HOST_FTDI") (pin "20") (pinfunction "GND_20") (pintype "power_in"))
      (node (ref "DVL_HOST_FTDI") (pin "24") (pinfunction "GND_24") (pintype "power_in"))
      (node (ref "DVL_HOST_FTDI") (pin "26") (pinfunction "TEST_26") (pintype "input"))
      (node (ref "DVL_HOST_FTDI") (pin "4") (pinfunction "GND_4") (pintype "power_in"))
      (node (ref "DVL_SLAVE_FTDI") (pin "17") (pinfunction "GND_17") (pintype "power_in"))
      (node (ref "DVL_SLAVE_FTDI") (pin "20") (pinfunction "GND_20") (pintype "power_in"))
      (node (ref "DVL_SLAVE_FTDI") (pin "24") (pinfunction "GND_24") (pintype "power_in"))
      (node (ref "DVL_SLAVE_FTDI") (pin "26") (pinfunction "TEST_26") (pintype "input"))
      (node (ref "DVL_SLAVE_FTDI") (pin "4") (pinfunction "GND_4") (pintype "power_in"))
      (node (ref "DVL_TTL-TO-RS232") (pin "10") (pinfunction "GND_10") (pintype "bidirectional"))
      (node (ref "DVL_USB_HUB") (pin "P$11") (pinfunction "PRTPWR2_P$11") (pintype "bidirectional"))
      (node (ref "DVL_USB_HUB") (pin "P$15") (pinfunction "VSS_P$15") (pintype "bidirectional"))
      (node (ref "DVL_USB_HUB") (pin "P$7") (pinfunction "PRTPWR1_P$7") (pintype "bidirectional"))
      (node (ref "IC1") (pin "4") (pinfunction "GND_4") (pintype "passive"))
      (node (ref "IMU_FTDI") (pin "17") (pinfunction "GND_17") (pintype "power_in"))
      (node (ref "IMU_FTDI") (pin "20") (pinfunction "GND_20") (pintype "power_in"))
      (node (ref "IMU_FTDI") (pin "24") (pinfunction "GND_24") (pintype "power_in"))
      (node (ref "IMU_FTDI") (pin "26") (pinfunction "TEST_26") (pintype "input"))
      (node (ref "IMU_FTDI") (pin "4") (pinfunction "GND_4") (pintype "power_in"))
      (node (ref "IMU_TTL-TO-RS422") (pin "P$14") (pinfunction "GND_P$14") (pintype "bidirectional"))
      (node (ref "IMU_TTL-TO-RS422") (pin "P$15") (pinfunction "232/~{422}_P$15") (pintype "bidirectional"))
      (node (ref "IMU_TTL-TO-RS422") (pin "P$18") (pinfunction "GND_P$18") (pintype "bidirectional"))
      (node (ref "JP1") (pin "12") (pinfunction "P$12_12") (pintype "bidirectional"))
      (node (ref "JP1") (pin "15") (pinfunction "P$15_15") (pintype "bidirectional"))
      (node (ref "JP1") (pin "18") (pinfunction "P$18_18") (pintype "bidirectional"))
      (node (ref "JP1") (pin "24") (pinfunction "P$24_24") (pintype "bidirectional"))
      (node (ref "JP1") (pin "33") (pinfunction "P$33_33") (pintype "bidirectional"))
      (node (ref "JP1") (pin "34") (pinfunction "P$34_34") (pintype "bidirectional"))
      (node (ref "JP1") (pin "36") (pinfunction "P$36_36") (pintype "bidirectional"))
      (node (ref "JP1") (pin "37") (pinfunction "P$37_37") (pintype "bidirectional"))
      (node (ref "JP1") (pin "39") (pinfunction "P$39_39") (pintype "bidirectional"))
      (node (ref "JP1") (pin "4") (pinfunction "P$4_4") (pintype "bidirectional"))
      (node (ref "JP1") (pin "44") (pinfunction "P$44_44") (pintype "bidirectional"))
      (node (ref "JP1") (pin "64") (pinfunction "P$64_64") (pintype "bidirectional"))
      (node (ref "JP1") (pin "P2,1") (pinfunction "POWER2_P2,1") (pintype "bidirectional"))
      (node (ref "JP1") (pin "P2,2") (pinfunction "POWER2_P2,2") (pintype "bidirectional"))
      (node (ref "JP1") (pin "P2,3") (pinfunction "POWER2_P2,3") (pintype "bidirectional"))
      (node (ref "JP1") (pin "P2,4") (pinfunction "POWER2_P2,4") (pintype "bidirectional"))
      (node (ref "JP1") (pin "P2,5") (pinfunction "POWER2_P2,5") (pintype "bidirectional"))
      (node (ref "JP1") (pin "P2,6") (pinfunction "POWER2_P2,6") (pintype "bidirectional"))
      (node (ref "JP2") (pin "12") (pinfunction "P$12_12") (pintype "bidirectional"))
      (node (ref "JP2") (pin "15") (pinfunction "P$15_15") (pintype "bidirectional"))
      (node (ref "JP2") (pin "18") (pinfunction "P$18_18") (pintype "bidirectional"))
      (node (ref "JP2") (pin "24") (pinfunction "P$24_24") (pintype "bidirectional"))
      (node (ref "JP2") (pin "33") (pinfunction "P$33_33") (pintype "bidirectional"))
      (node (ref "JP2") (pin "34") (pinfunction "P$34_34") (pintype "bidirectional"))
      (node (ref "JP2") (pin "36") (pinfunction "P$36_36") (pintype "bidirectional"))
      (node (ref "JP2") (pin "37") (pinfunction "P$37_37") (pintype "bidirectional"))
      (node (ref "JP2") (pin "39") (pinfunction "P$39_39") (pintype "bidirectional"))
      (node (ref "JP2") (pin "4") (pinfunction "P$4_4") (pintype "bidirectional"))
      (node (ref "JP2") (pin "44") (pinfunction "P$44_44") (pintype "bidirectional"))
      (node (ref "JP2") (pin "64") (pinfunction "P$64_64") (pintype "bidirectional"))
      (node (ref "JP2") (pin "P2,1") (pinfunction "POWER2_P2,1") (pintype "bidirectional"))
      (node (ref "JP2") (pin "P2,2") (pinfunction "POWER2_P2,2") (pintype "bidirectional"))
      (node (ref "JP2") (pin "P2,3") (pinfunction "POWER2_P2,3") (pintype "bidirectional"))
      (node (ref "JP2") (pin "P2,4") (pinfunction "POWER2_P2,4") (pintype "bidirectional"))
      (node (ref "JP2") (pin "P2,5") (pinfunction "POWER2_P2,5") (pintype "bidirectional"))
      (node (ref "JP2") (pin "P2,6") (pinfunction "POWER2_P2,6") (pintype "bidirectional"))
      (node (ref "JP3") (pin "12") (pinfunction "P$12_12") (pintype "bidirectional"))
      (node (ref "JP3") (pin "15") (pinfunction "P$15_15") (pintype "bidirectional"))
      (node (ref "JP3") (pin "18") (pinfunction "P$18_18") (pintype "bidirectional"))
      (node (ref "JP3") (pin "24") (pinfunction "P$24_24") (pintype "bidirectional"))
      (node (ref "JP3") (pin "33") (pinfunction "P$33_33") (pintype "bidirectional"))
      (node (ref "JP3") (pin "34") (pinfunction "P$34_34") (pintype "bidirectional"))
      (node (ref "JP3") (pin "36") (pinfunction "P$36_36") (pintype "bidirectional"))
      (node (ref "JP3") (pin "37") (pinfunction "P$37_37") (pintype "bidirectional"))
      (node (ref "JP3") (pin "39") (pinfunction "P$39_39") (pintype "bidirectional"))
      (node (ref "JP3") (pin "4") (pinfunction "P$4_4") (pintype "bidirectional"))
      (node (ref "JP3") (pin "44") (pinfunction "P$44_44") (pintype "bidirectional"))
      (node (ref "JP3") (pin "64") (pinfunction "P$64_64") (pintype "bidirectional"))
      (node (ref "JP3") (pin "P2,1") (pinfunction "POWER2_P2,1") (pintype "bidirectional"))
      (node (ref "JP3") (pin "P2,2") (pinfunction "POWER2_P2,2") (pintype "bidirectional"))
      (node (ref "JP3") (pin "P2,3") (pinfunction "POWER2_P2,3") (pintype "bidirectional"))
      (node (ref "JP3") (pin "P2,4") (pinfunction "POWER2_P2,4") (pintype "bidirectional"))
      (node (ref "JP3") (pin "P2,5") (pinfunction "POWER2_P2,5") (pintype "bidirectional"))
      (node (ref "JP3") (pin "P2,6") (pinfunction "POWER2_P2,6") (pintype "bidirectional"))
      (node (ref "JP4") (pin "12") (pinfunction "P$12_12") (pintype "bidirectional"))
      (node (ref "JP4") (pin "15") (pinfunction "P$15_15") (pintype "bidirectional"))
      (node (ref "JP4") (pin "18") (pinfunction "P$18_18") (pintype "bidirectional"))
      (node (ref "JP4") (pin "24") (pinfunction "P$24_24") (pintype "bidirectional"))
      (node (ref "JP4") (pin "33") (pinfunction "P$33_33") (pintype "bidirectional"))
      (node (ref "JP4") (pin "34") (pinfunction "P$34_34") (pintype "bidirectional"))
      (node (ref "JP4") (pin "36") (pinfunction "P$36_36") (pintype "bidirectional"))
      (node (ref "JP4") (pin "37") (pinfunction "P$37_37") (pintype "bidirectional"))
      (node (ref "JP4") (pin "39") (pinfunction "P$39_39") (pintype "bidirectional"))
      (node (ref "JP4") (pin "4") (pinfunction "P$4_4") (pintype "bidirectional"))
      (node (ref "JP4") (pin "44") (pinfunction "P$44_44") (pintype "bidirectional"))
      (node (ref "JP4") (pin "64") (pinfunction "P$64_64") (pintype "bidirectional"))
      (node (ref "JP4") (pin "P2,1") (pinfunction "POWER2_P2,1") (pintype "bidirectional"))
      (node (ref "JP4") (pin "P2,2") (pinfunction "POWER2_P2,2") (pintype "bidirectional"))
      (node (ref "JP4") (pin "P2,3") (pinfunction "POWER2_P2,3") (pintype "bidirectional"))
      (node (ref "JP4") (pin "P2,4") (pinfunction "POWER2_P2,4") (pintype "bidirectional"))
      (node (ref "JP4") (pin "P2,5") (pinfunction "POWER2_P2,5") (pintype "bidirectional"))
      (node (ref "JP4") (pin "P2,6") (pinfunction "POWER2_P2,6") (pintype "bidirectional"))
      (node (ref "R10") (pin "1") (pinfunction "1_1") (pintype "passive"))
      (node (ref "R12") (pin "1") (pinfunction "1_1") (pintype "passive"))
      (node (ref "R13") (pin "2") (pinfunction "2_2") (pintype "passive"))
      (node (ref "R14") (pin "2") (pinfunction "2_2") (pintype "passive"))
      (node (ref "R15") (pin "2") (pinfunction "2_2") (pintype "passive"))
      (node (ref "SYS-GND_0") (pin "P$1") (pinfunction "P$1_P$1") (pintype "bidirectional"))
      (node (ref "SYS-GND_0") (pin "P$2") (pinfunction "P$2_P$2") (pintype "bidirectional"))
      (node (ref "SYS-GND_1") (pin "P$1") (pinfunction "P$1_P$1") (pintype "bidirectional"))
      (node (ref "SYS-GND_1") (pin "P$2") (pinfunction "P$2_P$2") (pintype "bidirectional"))
      (node (ref "SYS-GND_2") (pin "P$1") (pinfunction "P$1_P$1") (pintype "bidirectional"))
      (node (ref "SYS-GND_2") (pin "P$2") (pinfunction "P$2_P$2") (pintype "bidirectional"))
      (node (ref "SYS-GND_3") (pin "P$1") (pinfunction "P$1_P$1") (pintype "bidirectional"))
      (node (ref "SYS-GND_3") (pin "P$2") (pinfunction "P$2_P$2") (pintype "bidirectional"))
      (node (ref "U$1") (pin "P$2") (pinfunction "GND_P$2") (pintype "bidirectional"))
      (node (ref "U$10") (pin "P$5") (pinfunction "5_P$5") (pintype "bidirectional"))
      (node (ref "U$11") (pin "P$2") (pinfunction "-_P$2") (pintype "bidirectional"))
      (node (ref "U$12") (pin "P$2") (pinfunction "-_P$2") (pintype "bidirectional"))
      (node (ref "U$15") (pin "P$1") (pinfunction "P$1_P$1") (pintype "bidirectional"))
      (node (ref "U$2") (pin "P$1") (pinfunction "GND_P$1") (pintype "bidirectional"))
      (node (ref "U$3") (pin "P$1") (pinfunction "GND_P$1") (pintype "bidirectional"))
      (node (ref "U$4") (pin "P$1") (pinfunction "GND_P$1") (pintype "bidirectional"))
      (node (ref "U$5") (pin "P$1") (pinfunction "GND_P$1") (pintype "bidirectional"))
      (node (ref "U$6") (pin "P$1") (pinfunction "GND_P$1") (pintype "bidirectional"))
      (node (ref "U$7") (pin "P$1") (pinfunction "GND_P$1") (pintype "bidirectional"))
      (node (ref "U$8") (pin "P$1") (pinfunction "GND_P$1") (pintype "bidirectional"))
      (node (ref "U$9") (pin "P$1") (pinfunction "GND_P$1") (pintype "bidirectional"))
    )
    (net (code "54") (name "/GND\\") (class "Default")
      (node (ref "DVL_USB_HUB") (pin "P$29") (pinfunction "GND_P$29") (pintype "bidirectional"))
      (node (ref "JP1") (pin "40") (pinfunction "P$40_40") (pintype "bidirectional"))
      (node (ref "JP2") (pin "40") (pinfunction "P$40_40") (pintype "bidirectional"))
      (node (ref "JP3") (pin "40") (pinfunction "P$40_40") (pintype "bidirectional"))
      (node (ref "JP4") (pin "40") (pinfunction "P$40_40") (pintype "bidirectional"))
    )
    (net (code "55") (name "/GPIO_0") (class "Default")
      (node (ref "JP1") (pin "35") (pinfunction "P$35_35") (pintype "bidirectional"))
      (node (ref "JP2") (pin "35") (pinfunction "P$35_35") (pintype "bidirectional"))
      (node (ref "JP3") (pin "35") (pinfunction "P$35_35") (pintype "bidirectional"))
      (node (ref "JP4") (pin "35") (pinfunction "P$35_35") (pintype "bidirectional"))
    )
    (net (code "56") (name "/GPIO_1") (class "Default")
      (node (ref "JP1") (pin "38") (pinfunction "P$38_38") (pintype "bidirectional"))
      (node (ref "JP2") (pin "38") (pinfunction "P$38_38") (pintype "bidirectional"))
      (node (ref "JP3") (pin "38") (pinfunction "P$38_38") (pintype "bidirectional"))
      (node (ref "JP4") (pin "38") (pinfunction "P$38_38") (pintype "bidirectional"))
    )
    (net (code "57") (name "/GPIO_2") (class "Default")
      (node (ref "JP1") (pin "11") (pinfunction "P$11_11") (pintype "bidirectional"))
      (node (ref "JP2") (pin "11") (pinfunction "P$11_11") (pintype "bidirectional"))
      (node (ref "JP3") (pin "11") (pinfunction "P$11_11") (pintype "bidirectional"))
      (node (ref "JP4") (pin "11") (pinfunction "P$11_11") (pintype "bidirectional"))
    )
    (net (code "58") (name "/GPIO_3") (class "Default")
      (node (ref "JP1") (pin "57") (pinfunction "P$57_57") (pintype "bidirectional"))
      (node (ref "JP2") (pin "57") (pinfunction "P$57_57") (pintype "bidirectional"))
      (node (ref "JP3") (pin "57") (pinfunction "P$57_57") (pintype "bidirectional"))
      (node (ref "JP4") (pin "57") (pinfunction "P$57_57") (pintype "bidirectional"))
    )
    (net (code "59") (name "/GPIO_4") (class "Default")
      (node (ref "JP1") (pin "58") (pinfunction "P$58_58") (pintype "bidirectional"))
      (node (ref "JP2") (pin "58") (pinfunction "P$58_58") (pintype "bidirectional"))
      (node (ref "JP3") (pin "58") (pinfunction "P$58_58") (pintype "bidirectional"))
      (node (ref "JP4") (pin "58") (pinfunction "P$58_58") (pintype "bidirectional"))
    )
    (net (code "60") (name "/HUB_USB_M") (class "Default")
      (node (ref "2PIN_1") (pin "P$2") (pinfunction "P$2_P$2") (pintype "bidirectional"))
      (node (ref "U$2") (pin "P$3") (pinfunction "I/O_2_P$3") (pintype "bidirectional"))
    )
    (net (code "61") (name "/HUB_USB_P") (class "Default")
      (node (ref "2PIN_1") (pin "P$1") (pinfunction "P$1_P$1") (pintype "bidirectional"))
      (node (ref "U$2") (pin "P$2") (pinfunction "I/O_1_P$2") (pintype "bidirectional"))
    )
    (net (code "62") (name "/IMU_RX") (class "Default")
      (node (ref "IMU_FTDI") (pin "2") (pinfunction "RXD_2") (pintype "input"))
      (node (ref "IMU_TTL-TO-RS422") (pin "P$17") (pinfunction "R1-OUT_P$17") (pintype "bidirectional"))
    )
    (net (code "63") (name "/IMU_RXD_M") (class "Default")
      (node (ref "IMU_TTL-TO-RS422") (pin "P$8") (pinfunction "R1-IN(B)_P$8") (pintype "bidirectional"))
      (node (ref "R1") (pin "1") (pinfunction "1_1") (pintype "passive"))
      (node (ref "U$10") (pin "P$4") (pinfunction "4_P$4") (pintype "bidirectional"))
      (node (ref "U$9") (pin "P$3") (pinfunction "I/O_2_P$3") (pintype "bidirectional"))
    )
    (net (code "64") (name "/IMU_RXD_P") (class "Default")
      (node (ref "IMU_TTL-TO-RS422") (pin "P$9") (pinfunction "R1-IN/(A)_P$9") (pintype "bidirectional"))
      (node (ref "R1") (pin "2") (pinfunction "2_2") (pintype "passive"))
      (node (ref "U$10") (pin "P$3") (pinfunction "3_P$3") (pintype "bidirectional"))
      (node (ref "U$9") (pin "P$2") (pinfunction "I/O_1_P$2") (pintype "bidirectional"))
    )
    (net (code "65") (name "/IMU_USB_M") (class "Default")
      (node (ref "2PIN_3") (pin "P$2") (pinfunction "P$2_P$2") (pintype "bidirectional"))
      (node (ref "IMU_FTDI") (pin "15") (pinfunction "USBDM_15") (pintype "bidirectional"))
      (node (ref "U$3") (pin "P$3") (pinfunction "I/O_2_P$3") (pintype "bidirectional"))
    )
    (net (code "66") (name "/IMU_USB_P") (class "Default")
      (node (ref "2PIN_3") (pin "P$1") (pinfunction "P$1_P$1") (pintype "bidirectional"))
      (node (ref "IMU_FTDI") (pin "14") (pinfunction "USBDP_14") (pintype "bidirectional"))
      (node (ref "U$3") (pin "P$2") (pinfunction "I/O_1_P$2") (pintype "bidirectional"))
    )
    (net (code "67") (name "/MISO") (class "Default")
      (node (ref "4PIN_7") (pin "P$3") (pinfunction "P$3_P$3") (pintype "bidirectional"))
      (node (ref "JP1") (pin "51") (pinfunction "P$51_51") (pintype "bidirectional"))
      (node (ref "JP2") (pin "51") (pinfunction "P$51_51") (pintype "bidirectional"))
      (node (ref "JP3") (pin "51") (pinfunction "P$51_51") (pintype "bidirectional"))
      (node (ref "JP4") (pin "51") (pinfunction "P$51_51") (pintype "bidirectional"))
      (node (ref "U$15") (pin "P$5") (pinfunction "P$5_P$5") (pintype "bidirectional"))
    )
    (net (code "68") (name "/MOSI") (class "Default")
      (node (ref "4PIN_7") (pin "P$4") (pinfunction "P$4_P$4") (pintype "bidirectional"))
      (node (ref "JP1") (pin "50") (pinfunction "P$50_50") (pintype "bidirectional"))
      (node (ref "JP2") (pin "50") (pinfunction "P$50_50") (pintype "bidirectional"))
      (node (ref "JP3") (pin "50") (pinfunction "P$50_50") (pintype "bidirectional"))
      (node (ref "JP4") (pin "50") (pinfunction "P$50_50") (pintype "bidirectional"))
      (node (ref "U$15") (pin "P$6") (pinfunction "P$6_P$6") (pintype "bidirectional"))
    )
    (net (code "69") (name "/NC") (class "Default")
      (node (ref "JP1") (pin "13") (pinfunction "P$13_13") (pintype "bidirectional"))
      (node (ref "JP1") (pin "14") (pinfunction "P$14_14") (pintype "bidirectional"))
      (node (ref "JP1") (pin "16") (pinfunction "P$16_16") (pintype "bidirectional"))
      (node (ref "JP1") (pin "17") (pinfunction "P$17_17") (pintype "bidirectional"))
      (node (ref "JP2") (pin "13") (pinfunction "P$13_13") (pintype "bidirectional"))
      (node (ref "JP2") (pin "14") (pinfunction "P$14_14") (pintype "bidirectional"))
      (node (ref "JP2") (pin "16") (pinfunction "P$16_16") (pintype "bidirectional"))
      (node (ref "JP2") (pin "17") (pinfunction "P$17_17") (pintype "bidirectional"))
      (node (ref "JP3") (pin "13") (pinfunction "P$13_13") (pintype "bidirectional"))
      (node (ref "JP3") (pin "14") (pinfunction "P$14_14") (pintype "bidirectional"))
      (node (ref "JP3") (pin "16") (pinfunction "P$16_16") (pintype "bidirectional"))
      (node (ref "JP3") (pin "17") (pinfunction "P$17_17") (pintype "bidirectional"))
      (node (ref "JP4") (pin "13") (pinfunction "P$13_13") (pintype "bidirectional"))
      (node (ref "JP4") (pin "14") (pinfunction "P$14_14") (pintype "bidirectional"))
      (node (ref "JP4") (pin "16") (pinfunction "P$16_16") (pintype "bidirectional"))
      (node (ref "JP4") (pin "17") (pinfunction "P$17_17") (pintype "bidirectional"))
    )
    (net (code "70") (name "/PWM_0") (class "Default")
      (node (ref "JP1") (pin "7") (pinfunction "P$7_7") (pintype "bidirectional"))
      (node (ref "JP2") (pin "7") (pinfunction "P$7_7") (pintype "bidirectional"))
      (node (ref "JP3") (pin "7") (pinfunction "P$7_7") (pintype "bidirectional"))
      (node (ref "JP4") (pin "7") (pinfunction "P$7_7") (pintype "bidirectional"))
    )
    (net (code "71") (name "/PWM_1") (class "Default")
      (node (ref "JP1") (pin "8") (pinfunction "P$8_8") (pintype "bidirectional"))
      (node (ref "JP2") (pin "8") (pinfunction "P$8_8") (pintype "bidirectional"))
      (node (ref "JP3") (pin "8") (pinfunction "P$8_8") (pintype "bidirectional"))
      (node (ref "JP4") (pin "8") (pinfunction "P$8_8") (pintype "bidirectional"))
    )
    (net (code "72") (name "/RTS_0") (class "Default")
      (node (ref "JP1") (pin "48") (pinfunction "P$48_48") (pintype "bidirectional"))
      (node (ref "JP2") (pin "48") (pinfunction "P$48_48") (pintype "bidirectional"))
      (node (ref "JP3") (pin "48") (pinfunction "P$48_48") (pintype "bidirectional"))
      (node (ref "JP4") (pin "48") (pinfunction "P$48_48") (pintype "bidirectional"))
    )
    (net (code "73") (name "/RTS_1") (class "Default")
      (node (ref "JP1") (pin "32") (pinfunction "P$32_32") (pintype "bidirectional"))
      (node (ref "JP2") (pin "32") (pinfunction "P$32_32") (pintype "bidirectional"))
      (node (ref "JP3") (pin "32") (pinfunction "P$32_32") (pintype "bidirectional"))
      (node (ref "JP4") (pin "32") (pinfunction "P$32_32") (pintype "bidirectional"))
    )
    (net (code "74") (name "/RTS_2") (class "Default")
      (node (ref "4PIN_1") (pin "P$2") (pinfunction "P$2_P$2") (pintype "bidirectional"))
      (node (ref "JP1") (pin "72") (pinfunction "P$72_72") (pintype "bidirectional"))
      (node (ref "JP2") (pin "72") (pinfunction "P$72_72") (pintype "bidirectional"))
      (node (ref "JP3") (pin "72") (pinfunction "P$72_72") (pintype "bidirectional"))
      (node (ref "JP4") (pin "72") (pinfunction "P$72_72") (pintype "bidirectional"))
    )
    (net (code "75") (name "/RTS_3") (class "Default")
      (node (ref "4PIN_2") (pin "P$2") (pinfunction "P$2_P$2") (pintype "bidirectional"))
      (node (ref "JP1") (pin "76") (pinfunction "P$76_76") (pintype "bidirectional"))
      (node (ref "JP2") (pin "76") (pinfunction "P$76_76") (pintype "bidirectional"))
      (node (ref "JP3") (pin "76") (pinfunction "P$76_76") (pintype "bidirectional"))
      (node (ref "JP4") (pin "76") (pinfunction "P$76_76") (pintype "bidirectional"))
    )
    (net (code "76") (name "/RTS_4") (class "Default")
      (node (ref "JP1") (pin "80") (pinfunction "P$80_80") (pintype "bidirectional"))
      (node (ref "JP2") (pin "80") (pinfunction "P$80_80") (pintype "bidirectional"))
      (node (ref "JP3") (pin "80") (pinfunction "P$80_80") (pintype "bidirectional"))
      (node (ref "JP4") (pin "80") (pinfunction "P$80_80") (pintype "bidirectional"))
    )
    (net (code "77") (name "/RTS_5") (class "Default")
      (node (ref "5.2") (pin "P$7") (pinfunction "P$4_P$7") (pintype "bidirectional"))
      (node (ref "5.2") (pin "P$8") (pinfunction "P$4_P$8") (pintype "bidirectional"))
      (node (ref "JP1") (pin "68") (pinfunction "P$68_68") (pintype "bidirectional"))
      (node (ref "JP2") (pin "68") (pinfunction "P$68_68") (pintype "bidirectional"))
      (node (ref "JP3") (pin "68") (pinfunction "P$68_68") (pintype "bidirectional"))
      (node (ref "JP4") (pin "68") (pinfunction "P$68_68") (pintype "bidirectional"))
    )
    (net (code "78") (name "/RX_0") (class "Default")
      (node (ref "JP1") (pin "45") (pinfunction "P$45_45") (pintype "bidirectional"))
      (node (ref "JP2") (pin "45") (pinfunction "P$45_45") (pintype "bidirectional"))
      (node (ref "JP3") (pin "45") (pinfunction "P$45_45") (pintype "bidirectional"))
      (node (ref "JP4") (pin "45") (pinfunction "P$45_45") (pintype "bidirectional"))
    )
    (net (code "79") (name "/RX_1") (class "Default")
      (node (ref "JP1") (pin "29") (pinfunction "P$29_29") (pintype "bidirectional"))
      (node (ref "JP2") (pin "29") (pinfunction "P$29_29") (pintype "bidirectional"))
      (node (ref "JP3") (pin "29") (pinfunction "P$29_29") (pintype "bidirectional"))
      (node (ref "JP4") (pin "29") (pinfunction "P$29_29") (pintype "bidirectional"))
    )
    (net (code "80") (name "/RX_2") (class "Default")
      (node (ref "4PIN_1") (pin "P$4") (pinfunction "P$4_P$4") (pintype "bidirectional"))
      (node (ref "JP1") (pin "69") (pinfunction "P$69_69") (pintype "bidirectional"))
      (node (ref "JP2") (pin "69") (pinfunction "P$69_69") (pintype "bidirectional"))
      (node (ref "JP3") (pin "69") (pinfunction "P$69_69") (pintype "bidirectional"))
      (node (ref "JP4") (pin "69") (pinfunction "P$69_69") (pintype "bidirectional"))
    )
    (net (code "81") (name "/RX_3") (class "Default")
      (node (ref "4PIN_2") (pin "P$4") (pinfunction "P$4_P$4") (pintype "bidirectional"))
      (node (ref "JP1") (pin "73") (pinfunction "P$73_73") (pintype "bidirectional"))
      (node (ref "JP2") (pin "73") (pinfunction "P$73_73") (pintype "bidirectional"))
      (node (ref "JP3") (pin "73") (pinfunction "P$73_73") (pintype "bidirectional"))
      (node (ref "JP4") (pin "73") (pinfunction "P$73_73") (pintype "bidirectional"))
    )
    (net (code "82") (name "/RX_4") (class "Default")
      (node (ref "JP1") (pin "77") (pinfunction "P$77_77") (pintype "bidirectional"))
      (node (ref "JP2") (pin "77") (pinfunction "P$77_77") (pintype "bidirectional"))
      (node (ref "JP3") (pin "77") (pinfunction "P$77_77") (pintype "bidirectional"))
      (node (ref "JP4") (pin "77") (pinfunction "P$77_77") (pintype "bidirectional"))
    )
    (net (code "83") (name "/RX_5") (class "Default")
      (node (ref "5.2") (pin "P$1") (pinfunction "P$1_P$1") (pintype "bidirectional"))
      (node (ref "5.2") (pin "P$2") (pinfunction "P$1_P$2") (pintype "bidirectional"))
      (node (ref "JP1") (pin "65") (pinfunction "P$65_65") (pintype "bidirectional"))
      (node (ref "JP2") (pin "65") (pinfunction "P$65_65") (pintype "bidirectional"))
      (node (ref "JP3") (pin "65") (pinfunction "P$65_65") (pintype "bidirectional"))
      (node (ref "JP4") (pin "65") (pinfunction "P$65_65") (pintype "bidirectional"))
    )
    (net (code "84") (name "/SCL_0") (class "Default")
      (node (ref "BATTERY-MUX") (pin "P$14") (pinfunction "SCL_P$14") (pintype "bidirectional"))
      (node (ref "JP1") (pin "28") (pinfunction "P$28_28") (pintype "bidirectional"))
      (node (ref "JP2") (pin "28") (pinfunction "P$28_28") (pintype "bidirectional"))
      (node (ref "JP3") (pin "28") (pinfunction "P$28_28") (pintype "bidirectional"))
      (node (ref "JP4") (pin "28") (pinfunction "P$28_28") (pintype "bidirectional"))
    )
    (net (code "85") (name "/SCL_1") (class "Default")
      (node (ref "2PIN_6") (pin "P$1") (pinfunction "P$1_P$1") (pintype "bidirectional"))
      (node (ref "JP1") (pin "10") (pinfunction "P$10_10") (pintype "bidirectional"))
      (node (ref "JP2") (pin "10") (pinfunction "P$10_10") (pintype "bidirectional"))
      (node (ref "JP3") (pin "10") (pinfunction "P$10_10") (pintype "bidirectional"))
      (node (ref "JP4") (pin "10") (pinfunction "P$10_10") (pintype "bidirectional"))
    )
    (net (code "86") (name "/SCL_2") (class "Default")
      (node (ref "5.4") (pin "P$10") (pinfunction "P$5_P$10") (pintype "bidirectional"))
      (node (ref "5.4") (pin "P$9") (pinfunction "P$5_P$9") (pintype "bidirectional"))
      (node (ref "JP1") (pin "60") (pinfunction "P$60_60") (pintype "bidirectional"))
      (node (ref "JP2") (pin "60") (pinfunction "P$60_60") (pintype "bidirectional"))
      (node (ref "JP3") (pin "60") (pinfunction "P$60_60") (pintype "bidirectional"))
      (node (ref "JP4") (pin "60") (pinfunction "P$60_60") (pintype "bidirectional"))
    )
    (net (code "87") (name "/SCL_3") (class "Default")
      (node (ref "5.3") (pin "P$3") (pinfunction "P$2_P$3") (pintype "bidirectional"))
      (node (ref "5.3") (pin "P$4") (pinfunction "P$2_P$4") (pintype "bidirectional"))
      (node (ref "JP1") (pin "6") (pinfunction "P$6_6") (pintype "bidirectional"))
      (node (ref "JP2") (pin "6") (pinfunction "P$6_6") (pintype "bidirectional"))
      (node (ref "JP3") (pin "6") (pinfunction "P$6_6") (pintype "bidirectional"))
      (node (ref "JP4") (pin "6") (pinfunction "P$6_6") (pintype "bidirectional"))
    )
    (net (code "88") (name "/SDA_0") (class "Default")
      (node (ref "BATTERY-MUX") (pin "P$15") (pinfunction "SDA_P$15") (pintype "bidirectional"))
      (node (ref "JP1") (pin "27") (pinfunction "P$27_27") (pintype "bidirectional"))
      (node (ref "JP2") (pin "27") (pinfunction "P$27_27") (pintype "bidirectional"))
      (node (ref "JP3") (pin "27") (pinfunction "P$27_27") (pintype "bidirectional"))
      (node (ref "JP4") (pin "27") (pinfunction "P$27_27") (pintype "bidirectional"))
    )
    (net (code "89") (name "/SDA_1") (class "Default")
      (node (ref "2PIN_6") (pin "P$2") (pinfunction "P$2_P$2") (pintype "bidirectional"))
      (node (ref "JP1") (pin "9") (pinfunction "P$9_9") (pintype "bidirectional"))
      (node (ref "JP2") (pin "9") (pinfunction "P$9_9") (pintype "bidirectional"))
      (node (ref "JP3") (pin "9") (pinfunction "P$9_9") (pintype "bidirectional"))
      (node (ref "JP4") (pin "9") (pinfunction "P$9_9") (pintype "bidirectional"))
    )
    (net (code "90") (name "/SDA_2") (class "Default")
      (node (ref "5.5") (pin "P$10") (pinfunction "P$5_P$10") (pintype "bidirectional"))
      (node (ref "5.5") (pin "P$9") (pinfunction "P$5_P$9") (pintype "bidirectional"))
      (node (ref "JP1") (pin "59") (pinfunction "P$59_59") (pintype "bidirectional"))
      (node (ref "JP2") (pin "59") (pinfunction "P$59_59") (pintype "bidirectional"))
      (node (ref "JP3") (pin "59") (pinfunction "P$59_59") (pintype "bidirectional"))
      (node (ref "JP4") (pin "59") (pinfunction "P$59_59") (pintype "bidirectional"))
    )
    (net (code "91") (name "/SDA_3") (class "Default")
      (node (ref "5.3") (pin "P$1") (pinfunction "P$1_P$1") (pintype "bidirectional"))
      (node (ref "5.3") (pin "P$2") (pinfunction "P$1_P$2") (pintype "bidirectional"))
      (node (ref "JP1") (pin "5") (pinfunction "P$5_5") (pintype "bidirectional"))
      (node (ref "JP2") (pin "5") (pinfunction "P$5_5") (pintype "bidirectional"))
      (node (ref "JP3") (pin "5") (pinfunction "P$5_5") (pintype "bidirectional"))
      (node (ref "JP4") (pin "5") (pinfunction "P$5_5") (pintype "bidirectional"))
    )
    (net (code "92") (name "/SHORE_SCL") (class "Default")
      (node (ref "5.4") (pin "P$3") (pinfunction "P$2_P$3") (pintype "bidirectional"))
      (node (ref "5.4") (pin "P$4") (pinfunction "P$2_P$4") (pintype "bidirectional"))
      (node (ref "BATTERY-MUX") (pin "P$5") (pinfunction "SC0_P$5") (pintype "bidirectional"))
    )
    (net (code "93") (name "/SHORE_SDA") (class "Default")
      (node (ref "5.5") (pin "P$3") (pinfunction "P$2_P$3") (pintype "bidirectional"))
      (node (ref "5.5") (pin "P$4") (pinfunction "P$2_P$4") (pintype "bidirectional"))
      (node (ref "BATTERY-MUX") (pin "P$4") (pinfunction "SD0_P$4") (pintype "bidirectional"))
    )
    (net (code "94") (name "/SPI_CLK") (class "Default")
      (node (ref "4PIN_7") (pin "P$1") (pinfunction "P$1_P$1") (pintype "bidirectional"))
      (node (ref "JP1") (pin "49") (pinfunction "P$49_49") (pintype "bidirectional"))
      (node (ref "JP2") (pin "49") (pinfunction "P$49_49") (pintype "bidirectional"))
      (node (ref "JP3") (pin "49") (pinfunction "P$49_49") (pintype "bidirectional"))
      (node (ref "JP4") (pin "49") (pinfunction "P$49_49") (pintype "bidirectional"))
      (node (ref "U$15") (pin "P$4") (pinfunction "P$4_P$4") (pintype "bidirectional"))
    )
    (net (code "95") (name "/TX_0") (class "Default")
      (node (ref "JP1") (pin "46") (pinfunction "P$46_46") (pintype "bidirectional"))
      (node (ref "JP2") (pin "46") (pinfunction "P$46_46") (pintype "bidirectional"))
      (node (ref "JP3") (pin "46") (pinfunction "P$46_46") (pintype "bidirectional"))
      (node (ref "JP4") (pin "46") (pinfunction "P$46_46") (pintype "bidirectional"))
    )
    (net (code "96") (name "/TX_1") (class "Default")
      (node (ref "JP1") (pin "30") (pinfunction "P$30_30") (pintype "bidirectional"))
      (node (ref "JP2") (pin "30") (pinfunction "P$30_30") (pintype "bidirectional"))
      (node (ref "JP3") (pin "30") (pinfunction "P$30_30") (pintype "bidirectional"))
      (node (ref "JP4") (pin "30") (pinfunction "P$30_30") (pintype "bidirectional"))
    )
    (net (code "97") (name "/TX_2") (class "Default")
      (node (ref "4PIN_1") (pin "P$3") (pinfunction "P$3_P$3") (pintype "bidirectional"))
      (node (ref "JP1") (pin "70") (pinfunction "P$70_70") (pintype "bidirectional"))
      (node (ref "JP2") (pin "70") (pinfunction "P$70_70") (pintype "bidirectional"))
      (node (ref "JP3") (pin "70") (pinfunction "P$70_70") (pintype "bidirectional"))
      (node (ref "JP4") (pin "70") (pinfunction "P$70_70") (pintype "bidirectional"))
    )
    (net (code "98") (name "/TX_3") (class "Default")
      (node (ref "4PIN_2") (pin "P$3") (pinfunction "P$3_P$3") (pintype "bidirectional"))
      (node (ref "JP1") (pin "74") (pinfunction "P$74_74") (pintype "bidirectional"))
      (node (ref "JP2") (pin "74") (pinfunction "P$74_74") (pintype "bidirectional"))
      (node (ref "JP3") (pin "74") (pinfunction "P$74_74") (pintype "bidirectional"))
      (node (ref "JP4") (pin "74") (pinfunction "P$74_74") (pintype "bidirectional"))
    )
    (net (code "99") (name "/TX_4") (class "Default")
      (node (ref "JP1") (pin "78") (pinfunction "P$78_78") (pintype "bidirectional"))
      (node (ref "JP2") (pin "78") (pinfunction "P$78_78") (pintype "bidirectional"))
      (node (ref "JP3") (pin "78") (pinfunction "P$78_78") (pintype "bidirectional"))
      (node (ref "JP4") (pin "78") (pinfunction "P$78_78") (pintype "bidirectional"))
    )
    (net (code "100") (name "/TX_5") (class "Default")
      (node (ref "5.2") (pin "P$3") (pinfunction "P$2_P$3") (pintype "bidirectional"))
      (node (ref "5.2") (pin "P$4") (pinfunction "P$2_P$4") (pintype "bidirectional"))
      (node (ref "JP1") (pin "66") (pinfunction "P$66_66") (pintype "bidirectional"))
      (node (ref "JP2") (pin "66") (pinfunction "P$66_66") (pintype "bidirectional"))
      (node (ref "JP3") (pin "66") (pinfunction "P$66_66") (pintype "bidirectional"))
      (node (ref "JP4") (pin "66") (pinfunction "P$66_66") (pintype "bidirectional"))
    )
    (net (code "101") (name "/USB_1_M") (class "Default")
      (node (ref "JP1") (pin "19") (pinfunction "P$19_19") (pintype "bidirectional"))
    )
    (net (code "102") (name "/USB_1_P") (class "Default")
      (node (ref "JP1") (pin "20") (pinfunction "P$20_20") (pintype "bidirectional"))
    )
    (net (code "103") (name "/USB_2_M") (class "Default")
      (node (ref "JP2") (pin "19") (pinfunction "P$19_19") (pintype "bidirectional"))
    )
    (net (code "104") (name "/USB_2_P") (class "Default")
      (node (ref "JP2") (pin "20") (pinfunction "P$20_20") (pintype "bidirectional"))
    )
    (net (code "105") (name "/USB_3_M") (class "Default")
      (node (ref "JP3") (pin "19") (pinfunction "P$19_19") (pintype "bidirectional"))
    )
    (net (code "106") (name "/USB_3_P") (class "Default")
      (node (ref "JP3") (pin "20") (pinfunction "P$20_20") (pintype "bidirectional"))
    )
    (net (code "107") (name "/USB_4_M") (class "Default")
      (node (ref "JP4") (pin "19") (pinfunction "P$19_19") (pintype "bidirectional"))
    )
    (net (code "108") (name "/USB_4_P") (class "Default")
      (node (ref "JP4") (pin "20") (pinfunction "P$20_20") (pintype "bidirectional"))
    )
    (net (code "109") (name "/V_BATT") (class "Default")
      (node (ref "4PIN_3") (pin "P$1") (pinfunction "P$1_P$1") (pintype "bidirectional"))
      (node (ref "4PIN_3") (pin "P$2") (pinfunction "P$2_P$2") (pintype "bidirectional"))
      (node (ref "4PIN_3") (pin "P$3") (pinfunction "P$3_P$3") (pintype "bidirectional"))
      (node (ref "4PIN_3") (pin "P$4") (pinfunction "P$4_P$4") (pintype "bidirectional"))
      (node (ref "4PIN_4") (pin "P$1") (pinfunction "P$1_P$1") (pintype "bidirectional"))
      (node (ref "4PIN_4") (pin "P$2") (pinfunction "P$2_P$2") (pintype "bidirectional"))
      (node (ref "4PIN_4") (pin "P$3") (pinfunction "P$3_P$3") (pintype "bidirectional"))
      (node (ref "4PIN_4") (pin "P$4") (pinfunction "P$4_P$4") (pintype "bidirectional"))
      (node (ref "JP1") (pin "P1,1") (pinfunction "POWER1_P1,1") (pintype "bidirectional"))
      (node (ref "JP1") (pin "P1,2") (pinfunction "POWER1_P1,2") (pintype "bidirectional"))
      (node (ref "JP1") (pin "P1,3") (pinfunction "POWER1_P1,3") (pintype "bidirectional"))
      (node (ref "JP1") (pin "P1,4") (pinfunction "POWER1_P1,4") (pintype "bidirectional"))
      (node (ref "JP1") (pin "P1,5") (pinfunction "POWER1_P1,5") (pintype "bidirectional"))
      (node (ref "JP1") (pin "P1,6") (pinfunction "POWER1_P1,6") (pintype "bidirectional"))
      (node (ref "JP2") (pin "P1,1") (pinfunction "POWER1_P1,1") (pintype "bidirectional"))
      (node (ref "JP2") (pin "P1,2") (pinfunction "POWER1_P1,2") (pintype "bidirectional"))
      (node (ref "JP2") (pin "P1,3") (pinfunction "POWER1_P1,3") (pintype "bidirectional"))
      (node (ref "JP2") (pin "P1,4") (pinfunction "POWER1_P1,4") (pintype "bidirectional"))
      (node (ref "JP2") (pin "P1,5") (pinfunction "POWER1_P1,5") (pintype "bidirectional"))
      (node (ref "JP2") (pin "P1,6") (pinfunction "POWER1_P1,6") (pintype "bidirectional"))
      (node (ref "JP3") (pin "P1,1") (pinfunction "POWER1_P1,1") (pintype "bidirectional"))
      (node (ref "JP3") (pin "P1,2") (pinfunction "POWER1_P1,2") (pintype "bidirectional"))
      (node (ref "JP3") (pin "P1,3") (pinfunction "POWER1_P1,3") (pintype "bidirectional"))
      (node (ref "JP3") (pin "P1,4") (pinfunction "POWER1_P1,4") (pintype "bidirectional"))
      (node (ref "JP3") (pin "P1,5") (pinfunction "POWER1_P1,5") (pintype "bidirectional"))
      (node (ref "JP3") (pin "P1,6") (pinfunction "POWER1_P1,6") (pintype "bidirectional"))
      (node (ref "JP4") (pin "P1,1") (pinfunction "POWER1_P1,1") (pintype "bidirectional"))
      (node (ref "JP4") (pin "P1,2") (pinfunction "POWER1_P1,2") (pintype "bidirectional"))
      (node (ref "JP4") (pin "P1,3") (pinfunction "POWER1_P1,3") (pintype "bidirectional"))
      (node (ref "JP4") (pin "P1,4") (pinfunction "POWER1_P1,4") (pintype "bidirectional"))
      (node (ref "JP4") (pin "P1,5") (pinfunction "POWER1_P1,5") (pintype "bidirectional"))
      (node (ref "JP4") (pin "P1,6") (pinfunction "POWER1_P1,6") (pintype "bidirectional"))
    )
    (net (code "110") (name "Net-(DVL_HOST_FTDI-3V3OUT)") (class "Default")
      (node (ref "C4") (pin "1") (pinfunction "1_1") (pintype "passive"))
      (node (ref "DVL_HOST_FTDI") (pin "16") (pinfunction "3V3OUT_16") (pintype "output"))
    )
    (net (code "111") (name "Net-(DVL_HOST_FTDI-CBUS0)") (class "Default")
      (node (ref "DVL_HOST_FTDI") (pin "22") (pinfunction "CBUS0_22") (pintype "bidirectional"))
      (node (ref "LED1") (pin "C") (pinfunction "C_C") (pintype "passive"))
    )
    (net (code "112") (name "Net-(DVL_HOST_FTDI-CBUS1)") (class "Default")
      (node (ref "DVL_HOST_FTDI") (pin "21") (pinfunction "CBUS1_21") (pintype "bidirectional"))
      (node (ref "LED2") (pin "C") (pinfunction "C_C") (pintype "passive"))
    )
    (net (code "113") (name "Net-(DVL_SLAVE_FTDI-3V3OUT)") (class "Default")
      (node (ref "C8") (pin "1") (pinfunction "1_1") (pintype "passive"))
      (node (ref "DVL_SLAVE_FTDI") (pin "16") (pinfunction "3V3OUT_16") (pintype "output"))
    )
    (net (code "114") (name "Net-(DVL_SLAVE_FTDI-CBUS0)") (class "Default")
      (node (ref "DVL_SLAVE_FTDI") (pin "22") (pinfunction "CBUS0_22") (pintype "bidirectional"))
      (node (ref "LED3") (pin "C") (pinfunction "C_C") (pintype "passive"))
    )
    (net (code "115") (name "Net-(DVL_SLAVE_FTDI-CBUS1)") (class "Default")
      (node (ref "DVL_SLAVE_FTDI") (pin "21") (pinfunction "CBUS1_21") (pintype "bidirectional"))
      (node (ref "LED4") (pin "C") (pinfunction "C_C") (pintype "passive"))
    )
    (net (code "116") (name "Net-(DVL_TTL-TO-RS232-C1+)") (class "Default")
      (node (ref "C18") (pin "1") (pinfunction "1_1") (pintype "passive"))
      (node (ref "DVL_TTL-TO-RS232") (pin "12") (pinfunction "C1+_12") (pintype "bidirectional"))
    )
    (net (code "117") (name "Net-(DVL_TTL-TO-RS232-C1-)") (class "Default")
      (node (ref "C18") (pin "2") (pinfunction "2_2") (pintype "passive"))
      (node (ref "DVL_TTL-TO-RS232") (pin "14") (pinfunction "C1-_14") (pintype "bidirectional"))
    )
    (net (code "118") (name "Net-(DVL_TTL-TO-RS232-C2+)") (class "Default")
      (node (ref "C20") (pin "1") (pinfunction "1_1") (pintype "passive"))
      (node (ref "DVL_TTL-TO-RS232") (pin "15") (pinfunction "C2+_15") (pintype "bidirectional"))
    )
    (net (code "119") (name "Net-(DVL_TTL-TO-RS232-C2-)") (class "Default")
      (node (ref "C20") (pin "2") (pinfunction "2_2") (pintype "passive"))
      (node (ref "DVL_TTL-TO-RS232") (pin "16") (pinfunction "C2-_16") (pintype "bidirectional"))
    )
    (net (code "120") (name "Net-(DVL_TTL-TO-RS232-V+)") (class "Default")
      (node (ref "C17") (pin "1") (pinfunction "1_1") (pintype "passive"))
      (node (ref "DVL_TTL-TO-RS232") (pin "13") (pinfunction "V+_13") (pintype "bidirectional"))
    )
    (net (code "121") (name "Net-(DVL_TTL-TO-RS232-V-)") (class "Default")
      (node (ref "C19") (pin "2") (pinfunction "2_2") (pintype "passive"))
      (node (ref "DVL_TTL-TO-RS232") (pin "17") (pinfunction "V-_17") (pintype "bidirectional"))
    )
    (net (code "122") (name "Net-(DVL_USB_HUB-CRFILT)") (class "Default")
      (node (ref "C27") (pin "1") (pinfunction "1_1") (pintype "passive"))
      (node (ref "DVL_USB_HUB") (pin "P$9") (pinfunction "CRFILT_P$9") (pintype "bidirectional"))
    )
    (net (code "123") (name "Net-(DVL_USB_HUB-HS_IND)") (class "Default")
      (node (ref "DVL_USB_HUB") (pin "P$16") (pinfunction "HS_IND_P$16") (pintype "bidirectional"))
      (node (ref "R10") (pin "2") (pinfunction "2_2") (pintype "passive"))
    )
    (net (code "124") (name "Net-(DVL_USB_HUB-NON_REM1)") (class "Default")
      (node (ref "DVL_USB_HUB") (pin "P$13") (pinfunction "NON_REM1_P$13") (pintype "bidirectional"))
      (node (ref "R15") (pin "1") (pinfunction "1_1") (pintype "passive"))
    )
    (net (code "125") (name "Net-(DVL_USB_HUB-PLLFILT)") (class "Default")
      (node (ref "C26") (pin "1") (pinfunction "1_1") (pintype "passive"))
      (node (ref "DVL_USB_HUB") (pin "P$25") (pinfunction "PLLFILT_P$25") (pintype "bidirectional"))
    )
    (net (code "126") (name "Net-(DVL_USB_HUB-RBIAS)") (class "Default")
      (node (ref "DVL_USB_HUB") (pin "P$26") (pinfunction "RBIAS_P$26") (pintype "bidirectional"))
      (node (ref "R12") (pin "2") (pinfunction "2_2") (pintype "passive"))
    )
    (net (code "127") (name "Net-(DVL_USB_HUB-RESET_N)") (class "Default")
      (node (ref "DVL_USB_HUB") (pin "P$17") (pinfunction "RESET_N_P$17") (pintype "bidirectional"))
      (node (ref "R11") (pin "1") (pinfunction "1_1") (pintype "passive"))
    )
    (net (code "128") (name "Net-(DVL_USB_HUB-SUSP_IND{slash}NON_REM0)") (class "Default")
      (node (ref "DVL_USB_HUB") (pin "P$19") (pinfunction "SUSP_IND/NON_REM0_P$19") (pintype "bidirectional"))
      (node (ref "LED7") (pin "A") (pinfunction "A_A") (pintype "passive"))
      (node (ref "R14") (pin "1") (pinfunction "1_1") (pintype "passive"))
    )
    (net (code "129") (name "Net-(IMU_FTDI-3V3OUT)") (class "Default")
      (node (ref "C12") (pin "1") (pinfunction "1_1") (pintype "passive"))
      (node (ref "IMU_FTDI") (pin "16") (pinfunction "3V3OUT_16") (pintype "output"))
    )
    (net (code "130") (name "Net-(IMU_FTDI-CBUS0)") (class "Default")
      (node (ref "IMU_FTDI") (pin "22") (pinfunction "CBUS0_22") (pintype "bidirectional"))
      (node (ref "LED5") (pin "C") (pinfunction "C_C") (pintype "passive"))
    )
    (net (code "131") (name "Net-(IMU_FTDI-CBUS1)") (class "Default")
      (node (ref "IMU_FTDI") (pin "21") (pinfunction "CBUS1_21") (pintype "bidirectional"))
      (node (ref "LED6") (pin "C") (pinfunction "C_C") (pintype "passive"))
    )
    (net (code "132") (name "Net-(IMU_TTL-TO-RS422-C1+)") (class "Default")
      (node (ref "C23") (pin "1") (pinfunction "1_1") (pintype "passive"))
      (node (ref "IMU_TTL-TO-RS422") (pin "P$2") (pinfunction "C1+_P$2") (pintype "bidirectional"))
    )
    (net (code "133") (name "Net-(IMU_TTL-TO-RS422-C1-)") (class "Default")
      (node (ref "C23") (pin "2") (pinfunction "2_2") (pintype "passive"))
      (node (ref "IMU_TTL-TO-RS422") (pin "P$3") (pinfunction "C1-_P$3") (pintype "bidirectional"))
    )
    (net (code "134") (name "Net-(IMU_TTL-TO-RS422-C2+)") (class "Default")
      (node (ref "C24") (pin "1") (pinfunction "1_1") (pintype "passive"))
      (node (ref "IMU_TTL-TO-RS422") (pin "P$22") (pinfunction "C2+_P$22") (pintype "bidirectional"))
    )
    (net (code "135") (name "Net-(IMU_TTL-TO-RS422-C2-)") (class "Default")
      (node (ref "C24") (pin "2") (pinfunction "2_2") (pintype "passive"))
      (node (ref "IMU_TTL-TO-RS422") (pin "P$23") (pinfunction "C2-_P$23") (pintype "bidirectional"))
    )
    (net (code "136") (name "Net-(IMU_TTL-TO-RS422-V+)") (class "Default")
      (node (ref "C21") (pin "1") (pinfunction "1_1") (pintype "passive"))
      (node (ref "IMU_TTL-TO-RS422") (pin "P$1") (pinfunction "V+_P$1") (pintype "bidirectional"))
    )
    (net (code "137") (name "Net-(IMU_TTL-TO-RS422-V-)") (class "Default")
      (node (ref "C22") (pin "1") (pinfunction "1_1") (pintype "passive"))
      (node (ref "IMU_TTL-TO-RS422") (pin "P$24") (pinfunction "V-_P$24") (pintype "bidirectional"))
    )
    (net (code "138") (name "Net-(LED1-PadA)") (class "Default")
      (node (ref "LED1") (pin "A") (pinfunction "A_A") (pintype "passive"))
      (node (ref "R4") (pin "1") (pinfunction "1_1") (pintype "passive"))
    )
    (net (code "139") (name "Net-(LED2-PadA)") (class "Default")
      (node (ref "LED2") (pin "A") (pinfunction "A_A") (pintype "passive"))
      (node (ref "R5") (pin "1") (pinfunction "1_1") (pintype "passive"))
    )
    (net (code "140") (name "Net-(LED3-PadA)") (class "Default")
      (node (ref "LED3") (pin "A") (pinfunction "A_A") (pintype "passive"))
      (node (ref "R6") (pin "1") (pinfunction "1_1") (pintype "passive"))
    )
    (net (code "141") (name "Net-(LED4-PadA)") (class "Default")
      (node (ref "LED4") (pin "A") (pinfunction "A_A") (pintype "passive"))
      (node (ref "R7") (pin "1") (pinfunction "1_1") (pintype "passive"))
    )
    (net (code "142") (name "Net-(LED5-PadA)") (class "Default")
      (node (ref "LED5") (pin "A") (pinfunction "A_A") (pintype "passive"))
      (node (ref "R8") (pin "1") (pinfunction "1_1") (pintype "passive"))
    )
    (net (code "143") (name "Net-(LED6-PadA)") (class "Default")
      (node (ref "LED6") (pin "A") (pinfunction "A_A") (pintype "passive"))
      (node (ref "R9") (pin "1") (pinfunction "1_1") (pintype "passive"))
    )
    (net (code "144") (name "Net-(LED7-PadC)") (class "Default")
      (node (ref "LED7") (pin "C") (pinfunction "C_C") (pintype "passive"))
      (node (ref "R13") (pin "1") (pinfunction "1_1") (pintype "passive"))
    )
    (net (code "145") (name "unconnected-(BATTERY-MUX-SC3-PadP$12)") (class "Default")
      (node (ref "BATTERY-MUX") (pin "P$12") (pinfunction "SC3_P$12") (pintype "bidirectional"))
    )
    (net (code "146") (name "unconnected-(BATTERY-MUX-SD3-PadP$11)") (class "Default")
      (node (ref "BATTERY-MUX") (pin "P$11") (pinfunction "SD3_P$11") (pintype "bidirectional"))
    )
    (net (code "147") (name "unconnected-(DVL_HOST_FTDI-CBUS2-Pad10)") (class "Default")
      (node (ref "DVL_HOST_FTDI") (pin "10") (pinfunction "CBUS2_10") (pintype "bidirectional"))
    )
    (net (code "148") (name "unconnected-(DVL_HOST_FTDI-CBUS3-Pad11)") (class "Default")
      (node (ref "DVL_HOST_FTDI") (pin "11") (pinfunction "CBUS3_11") (pintype "bidirectional"))
    )
    (net (code "149") (name "unconnected-(DVL_HOST_FTDI-CBUS4-Pad9)") (class "Default")
      (node (ref "DVL_HOST_FTDI") (pin "9") (pinfunction "CBUS4_9") (pintype "bidirectional"))
    )
    (net (code "150") (name "unconnected-(DVL_HOST_FTDI-OSCI-Pad27)") (class "Default")
      (node (ref "DVL_HOST_FTDI") (pin "27") (pinfunction "OSCI_27") (pintype "input"))
    )
    (net (code "151") (name "unconnected-(DVL_HOST_FTDI-OSCO-Pad28)") (class "Default")
      (node (ref "DVL_HOST_FTDI") (pin "28") (pinfunction "OSCO_28") (pintype "output"))
    )
    (net (code "152") (name "unconnected-(DVL_HOST_FTDI-~{DCD}-Pad7)") (class "Default")
      (node (ref "DVL_HOST_FTDI") (pin "7") (pinfunction "~{DCD}_7") (pintype "input"))
    )
    (net (code "153") (name "unconnected-(DVL_HOST_FTDI-~{DSR}-Pad6)") (class "Default")
      (node (ref "DVL_HOST_FTDI") (pin "6") (pinfunction "~{DSR}_6") (pintype "input"))
    )
    (net (code "154") (name "unconnected-(DVL_HOST_FTDI-~{DTR}-Pad31)") (class "Default")
      (node (ref "DVL_HOST_FTDI") (pin "31") (pinfunction "~{DTR}_31") (pintype "output"))
    )
    (net (code "155") (name "unconnected-(DVL_HOST_FTDI-~{RI}-Pad3)") (class "Default")
      (node (ref "DVL_HOST_FTDI") (pin "3") (pinfunction "~{RI}_3") (pintype "input"))
    )
    (net (code "156") (name "unconnected-(DVL_SLAVE_FTDI-CBUS2-Pad10)") (class "Default")
      (node (ref "DVL_SLAVE_FTDI") (pin "10") (pinfunction "CBUS2_10") (pintype "bidirectional"))
    )
    (net (code "157") (name "unconnected-(DVL_SLAVE_FTDI-CBUS3-Pad11)") (class "Default")
      (node (ref "DVL_SLAVE_FTDI") (pin "11") (pinfunction "CBUS3_11") (pintype "bidirectional"))
    )
    (net (code "158") (name "unconnected-(DVL_SLAVE_FTDI-CBUS4-Pad9)") (class "Default")
      (node (ref "DVL_SLAVE_FTDI") (pin "9") (pinfunction "CBUS4_9") (pintype "bidirectional"))
    )
    (net (code "159") (name "unconnected-(DVL_SLAVE_FTDI-OSCI-Pad27)") (class "Default")
      (node (ref "DVL_SLAVE_FTDI") (pin "27") (pinfunction "OSCI_27") (pintype "input"))
    )
    (net (code "160") (name "unconnected-(DVL_SLAVE_FTDI-OSCO-Pad28)") (class "Default")
      (node (ref "DVL_SLAVE_FTDI") (pin "28") (pinfunction "OSCO_28") (pintype "output"))
    )
    (net (code "161") (name "unconnected-(DVL_SLAVE_FTDI-~{DCD}-Pad7)") (class "Default")
      (node (ref "DVL_SLAVE_FTDI") (pin "7") (pinfunction "~{DCD}_7") (pintype "input"))
    )
    (net (code "162") (name "unconnected-(DVL_SLAVE_FTDI-~{DSR}-Pad6)") (class "Default")
      (node (ref "DVL_SLAVE_FTDI") (pin "6") (pinfunction "~{DSR}_6") (pintype "input"))
    )
    (net (code "163") (name "unconnected-(DVL_SLAVE_FTDI-~{DTR}-Pad31)") (class "Default")
      (node (ref "DVL_SLAVE_FTDI") (pin "31") (pinfunction "~{DTR}_31") (pintype "output"))
    )
    (net (code "164") (name "unconnected-(DVL_SLAVE_FTDI-~{RI}-Pad3)") (class "Default")
      (node (ref "DVL_SLAVE_FTDI") (pin "3") (pinfunction "~{RI}_3") (pintype "input"))
    )
    (net (code "165") (name "unconnected-(DVL_TTL-TO-RS232-RIN5-Pad18)") (class "Default")
      (node (ref "DVL_TTL-TO-RS232") (pin "18") (pinfunction "RIN5_18") (pintype "bidirectional"))
    )
    (net (code "166") (name "unconnected-(DVL_TTL-TO-RS232-ROUT5-Pad19)") (class "Default")
      (node (ref "DVL_TTL-TO-RS232") (pin "19") (pinfunction "ROUT5_19") (pintype "bidirectional"))
    )
    (net (code "167") (name "unconnected-(DVL_USB_HUB-NC-PadP$5)") (class "Default")
      (node (ref "DVL_USB_HUB") (pin "P$5") (pinfunction "NC_P$5") (pintype "bidirectional"))
    )
    (net (code "168") (name "unconnected-(DVL_USB_HUB-NC-PadP$6)") (class "Default")
      (node (ref "DVL_USB_HUB") (pin "P$6") (pinfunction "NC_P$6") (pintype "bidirectional"))
    )
    (net (code "169") (name "unconnected-(DVL_USB_HUB-OCS_N1-PadP$8)") (class "Default")
      (node (ref "DVL_USB_HUB") (pin "P$8") (pinfunction "OCS_N1_P$8") (pintype "bidirectional"))
    )
    (net (code "170") (name "unconnected-(DVL_USB_HUB-OCS_N2-PadP$12)") (class "Default")
      (node (ref "DVL_USB_HUB") (pin "P$12") (pinfunction "OCS_N2_P$12") (pintype "bidirectional"))
    )
    (net (code "171") (name "unconnected-(DVL_USB_HUB-XTALOUT-PadP$23)") (class "Default")
      (node (ref "DVL_USB_HUB") (pin "P$23") (pinfunction "XTALOUT_P$23") (pintype "bidirectional"))
    )
    (net (code "172") (name "unconnected-(G1-PadGND1)") (class "Default")
      (node (ref "G1") (pin "GND1") (pinfunction "GND1_GND1") (pintype "bidirectional"))
    )
    (net (code "173") (name "unconnected-(G1-PadGND2)") (class "Default")
      (node (ref "G1") (pin "GND2") (pinfunction "GND2_GND2") (pintype "bidirectional"))
    )
    (net (code "174") (name "unconnected-(G1-PadIN1)") (class "Default")
      (node (ref "G1") (pin "IN1") (pinfunction "IN1_IN1") (pintype "bidirectional"))
    )
    (net (code "175") (name "unconnected-(G1-PadIN2)") (class "Default")
      (node (ref "G1") (pin "IN2") (pinfunction "IN2_IN2") (pintype "bidirectional"))
    )
    (net (code "176") (name "unconnected-(G1-PadOUT1)") (class "Default")
      (node (ref "G1") (pin "OUT1") (pinfunction "OUT1_OUT1") (pintype "bidirectional"))
    )
    (net (code "177") (name "unconnected-(G1-PadOUT2)") (class "Default")
      (node (ref "G1") (pin "OUT2") (pinfunction "OUT2_OUT2") (pintype "bidirectional"))
    )
    (net (code "178") (name "unconnected-(G1-PadOUT3)") (class "Default")
      (node (ref "G1") (pin "OUT3") (pinfunction "OUT3_OUT3") (pintype "bidirectional"))
    )
    (net (code "179") (name "unconnected-(G1-PadOUT4)") (class "Default")
      (node (ref "G1") (pin "OUT4") (pinfunction "OUT4_OUT4") (pintype "bidirectional"))
    )
    (net (code "180") (name "unconnected-(G1-~{EN1}-Pad!EN1!)") (class "Default")
      (node (ref "G1") (pin "!EN1!") (pinfunction "~{EN1}_!EN1!") (pintype "bidirectional"))
    )
    (net (code "181") (name "unconnected-(G1-~{EN2}-Pad!EN2!)") (class "Default")
      (node (ref "G1") (pin "!EN2!") (pinfunction "~{EN2}_!EN2!") (pintype "bidirectional"))
    )
    (net (code "182") (name "unconnected-(G1-~{EN3}-Pad!EN3!)") (class "Default")
      (node (ref "G1") (pin "!EN3!") (pinfunction "~{EN3}_!EN3!") (pintype "bidirectional"))
    )
    (net (code "183") (name "unconnected-(G1-~{EN4}-Pad!EN4!)") (class "Default")
      (node (ref "G1") (pin "!EN4!") (pinfunction "~{EN4}_!EN4!") (pintype "bidirectional"))
    )
    (net (code "184") (name "unconnected-(G1-~{OC1}-Pad!OC1!)") (class "Default")
      (node (ref "G1") (pin "!OC1!") (pinfunction "~{OC1}_!OC1!") (pintype "bidirectional"))
    )
    (net (code "185") (name "unconnected-(G1-~{OC2}-Pad!OC2!)") (class "Default")
      (node (ref "G1") (pin "!OC2!") (pinfunction "~{OC2}_!OC2!") (pintype "bidirectional"))
    )
    (net (code "186") (name "unconnected-(G1-~{OC3}-Pad!OC3!)") (class "Default")
      (node (ref "G1") (pin "!OC3!") (pinfunction "~{OC3}_!OC3!") (pintype "bidirectional"))
    )
    (net (code "187") (name "unconnected-(G1-~{OC4}-Pad!OC4!)") (class "Default")
      (node (ref "G1") (pin "!OC4!") (pinfunction "~{OC4}_!OC4!") (pintype "bidirectional"))
    )
    (net (code "188") (name "unconnected-(IMU_FTDI-CBUS2-Pad10)") (class "Default")
      (node (ref "IMU_FTDI") (pin "10") (pinfunction "CBUS2_10") (pintype "bidirectional"))
    )
    (net (code "189") (name "unconnected-(IMU_FTDI-CBUS3-Pad11)") (class "Default")
      (node (ref "IMU_FTDI") (pin "11") (pinfunction "CBUS3_11") (pintype "bidirectional"))
    )
    (net (code "190") (name "unconnected-(IMU_FTDI-CBUS4-Pad9)") (class "Default")
      (node (ref "IMU_FTDI") (pin "9") (pinfunction "CBUS4_9") (pintype "bidirectional"))
    )
    (net (code "191") (name "unconnected-(IMU_FTDI-OSCI-Pad27)") (class "Default")
      (node (ref "IMU_FTDI") (pin "27") (pinfunction "OSCI_27") (pintype "input"))
    )
    (net (code "192") (name "unconnected-(IMU_FTDI-OSCO-Pad28)") (class "Default")
      (node (ref "IMU_FTDI") (pin "28") (pinfunction "OSCO_28") (pintype "output"))
    )
    (net (code "193") (name "unconnected-(IMU_FTDI-TXD-Pad30)") (class "Default")
      (node (ref "IMU_FTDI") (pin "30") (pinfunction "TXD_30") (pintype "output"))
    )
    (net (code "194") (name "unconnected-(IMU_FTDI-~{CTS}-Pad8)") (class "Default")
      (node (ref "IMU_FTDI") (pin "8") (pinfunction "~{CTS}_8") (pintype "input"))
    )
    (net (code "195") (name "unconnected-(IMU_FTDI-~{DCD}-Pad7)") (class "Default")
      (node (ref "IMU_FTDI") (pin "7") (pinfunction "~{DCD}_7") (pintype "input"))
    )
    (net (code "196") (name "unconnected-(IMU_FTDI-~{DSR}-Pad6)") (class "Default")
      (node (ref "IMU_FTDI") (pin "6") (pinfunction "~{DSR}_6") (pintype "input"))
    )
    (net (code "197") (name "unconnected-(IMU_FTDI-~{DTR}-Pad31)") (class "Default")
      (node (ref "IMU_FTDI") (pin "31") (pinfunction "~{DTR}_31") (pintype "output"))
    )
    (net (code "198") (name "unconnected-(IMU_FTDI-~{RI}-Pad3)") (class "Default")
      (node (ref "IMU_FTDI") (pin "3") (pinfunction "~{RI}_3") (pintype "input"))
    )
    (net (code "199") (name "unconnected-(IMU_FTDI-~{RTS}-Pad32)") (class "Default")
      (node (ref "IMU_FTDI") (pin "32") (pinfunction "~{RTS}_32") (pintype "output"))
    )
    (net (code "200") (name "unconnected-(IMU_TTL-TO-RS422-NC-PadP$12)") (class "Default")
      (node (ref "IMU_TTL-TO-RS422") (pin "P$12") (pinfunction "NC_P$12") (pintype "bidirectional"))
    )
    (net (code "201") (name "unconnected-(IMU_TTL-TO-RS422-NC-PadP$13)") (class "Default")
      (node (ref "IMU_TTL-TO-RS422") (pin "P$13") (pinfunction "NC_P$13") (pintype "bidirectional"))
    )
    (net (code "202") (name "unconnected-(IMU_TTL-TO-RS422-R2-IN-PadP$4)") (class "Default")
      (node (ref "IMU_TTL-TO-RS422") (pin "P$4") (pinfunction "R2-IN_P$4") (pintype "bidirectional"))
    )
    (net (code "203") (name "unconnected-(IMU_TTL-TO-RS422-R2-OUT-PadP$21)") (class "Default")
      (node (ref "IMU_TTL-TO-RS422") (pin "P$21") (pinfunction "R2-OUT_P$21") (pintype "bidirectional"))
    )
    (net (code "204") (name "unconnected-(IMU_TTL-TO-RS422-T1-IN-PadP$20)") (class "Default")
      (node (ref "IMU_TTL-TO-RS422") (pin "P$20") (pinfunction "T1-IN_P$20") (pintype "bidirectional"))
    )
    (net (code "205") (name "unconnected-(IMU_TTL-TO-RS422-T1-OUT-PadP$5)") (class "Default")
      (node (ref "IMU_TTL-TO-RS422") (pin "P$5") (pinfunction "T1-OUT_P$5") (pintype "bidirectional"))
    )
    (net (code "206") (name "unconnected-(IMU_TTL-TO-RS422-T2-IN-PadP$19)") (class "Default")
      (node (ref "IMU_TTL-TO-RS422") (pin "P$19") (pinfunction "T2-IN_P$19") (pintype "bidirectional"))
    )
    (net (code "207") (name "unconnected-(IMU_TTL-TO-RS422-T2-OUT-PadP$6)") (class "Default")
      (node (ref "IMU_TTL-TO-RS422") (pin "P$6") (pinfunction "T2-OUT_P$6") (pintype "bidirectional"))
    )
    (net (code "208") (name "unconnected-(IMU_TTL-TO-RS422-T3-IN-PadP$16)") (class "Default")
      (node (ref "IMU_TTL-TO-RS422") (pin "P$16") (pinfunction "T3-IN_P$16") (pintype "bidirectional"))
    )
    (net (code "209") (name "unconnected-(IMU_TTL-TO-RS422-T3-OUT(A)-PadP$11)") (class "Default")
      (node (ref "IMU_TTL-TO-RS422") (pin "P$11") (pinfunction "T3-OUT(A)_P$11") (pintype "bidirectional"))
    )
    (net (code "210") (name "unconnected-(IMU_TTL-TO-RS422-T3-OUT(B)-PadP$10)") (class "Default")
      (node (ref "IMU_TTL-TO-RS422") (pin "P$10") (pinfunction "T3-OUT(B)_P$10") (pintype "bidirectional"))
    )
    (net (code "211") (name "unconnected-(U$4-I{slash}O_1-PadP$2)") (class "Default")
      (node (ref "U$4") (pin "P$2") (pinfunction "I/O_1_P$2") (pintype "bidirectional"))
    )
    (net (code "212") (name "unconnected-(U$4-I{slash}O_2-PadP$3)") (class "Default")
      (node (ref "U$4") (pin "P$3") (pinfunction "I/O_2_P$3") (pintype "bidirectional"))
    )
    (net (code "213") (name "unconnected-(U$8-I{slash}O_1-PadP$2)") (class "Default")
      (node (ref "U$8") (pin "P$2") (pinfunction "I/O_1_P$2") (pintype "bidirectional"))
    )
    (net (code "214") (name "unconnected-(U$8-I{slash}O_2-PadP$3)") (class "Default")
      (node (ref "U$8") (pin "P$3") (pinfunction "I/O_2_P$3") (pintype "bidirectional"))
    )
    (net (code "215") (name "unconnected-(U$10-1-PadP$1)") (class "Default")
      (node (ref "U$10") (pin "P$1") (pinfunction "1_P$1") (pintype "bidirectional"))
    )
    (net (code "216") (name "unconnected-(U$10-6-PadP$6)") (class "Default")
      (node (ref "U$10") (pin "P$6") (pinfunction "6_P$6") (pintype "bidirectional"))
    )
    (net (code "217") (name "unconnected-(U1-DM0-PadP$4)") (class "Default")
      (node (ref "U1") (pin "P$4") (pinfunction "DM0_P$4") (pintype "bidirectional"))
    )
    (net (code "218") (name "unconnected-(U1-DM1-PadP$13)") (class "Default")
      (node (ref "U1") (pin "P$13") (pinfunction "DM1_P$13") (pintype "bidirectional"))
    )
    (net (code "219") (name "unconnected-(U1-DM2-PadP$17)") (class "Default")
      (node (ref "U1") (pin "P$17") (pinfunction "DM2_P$17") (pintype "bidirectional"))
    )
    (net (code "220") (name "unconnected-(U1-DM3-PadP$21)") (class "Default")
      (node (ref "U1") (pin "P$21") (pinfunction "DM3_P$21") (pintype "bidirectional"))
    )
    (net (code "221") (name "unconnected-(U1-DM4-PadP$26)") (class "Default")
      (node (ref "U1") (pin "P$26") (pinfunction "DM4_P$26") (pintype "bidirectional"))
    )
    (net (code "222") (name "unconnected-(U1-DM5-PadP$30)") (class "Default")
      (node (ref "U1") (pin "P$30") (pinfunction "DM5_P$30") (pintype "bidirectional"))
    )
    (net (code "223") (name "unconnected-(U1-DM6-PadP$34)") (class "Default")
      (node (ref "U1") (pin "P$34") (pinfunction "DM6_P$34") (pintype "bidirectional"))
    )
    (net (code "224") (name "unconnected-(U1-DM7-PadP$38)") (class "Default")
      (node (ref "U1") (pin "P$38") (pinfunction "DM7_P$38") (pintype "bidirectional"))
    )
    (net (code "225") (name "unconnected-(U1-DP0-PadP$3)") (class "Default")
      (node (ref "U1") (pin "P$3") (pinfunction "DP0_P$3") (pintype "bidirectional"))
    )
    (net (code "226") (name "unconnected-(U1-DP0PUR-PadP$2)") (class "Default")
      (node (ref "U1") (pin "P$2") (pinfunction "DP0PUR_P$2") (pintype "bidirectional"))
    )
    (net (code "227") (name "unconnected-(U1-DP1-PadP$14)") (class "Default")
      (node (ref "U1") (pin "P$14") (pinfunction "DP1_P$14") (pintype "bidirectional"))
    )
    (net (code "228") (name "unconnected-(U1-DP2-PadP$18)") (class "Default")
      (node (ref "U1") (pin "P$18") (pinfunction "DP2_P$18") (pintype "bidirectional"))
    )
    (net (code "229") (name "unconnected-(U1-DP3-PadP$22)") (class "Default")
      (node (ref "U1") (pin "P$22") (pinfunction "DP3_P$22") (pintype "bidirectional"))
    )
    (net (code "230") (name "unconnected-(U1-DP4-PadP$27)") (class "Default")
      (node (ref "U1") (pin "P$27") (pinfunction "DP4_P$27") (pintype "bidirectional"))
    )
    (net (code "231") (name "unconnected-(U1-DP5-PadP$31)") (class "Default")
      (node (ref "U1") (pin "P$31") (pinfunction "DP5_P$31") (pintype "bidirectional"))
    )
    (net (code "232") (name "unconnected-(U1-DP6-PadP$35)") (class "Default")
      (node (ref "U1") (pin "P$35") (pinfunction "DP6_P$35") (pintype "bidirectional"))
    )
    (net (code "233") (name "unconnected-(U1-DP7-PadP$39)") (class "Default")
      (node (ref "U1") (pin "P$39") (pinfunction "DP7_P$39") (pintype "bidirectional"))
    )
    (net (code "234") (name "unconnected-(U1-EECLK-PadP$7)") (class "Default")
      (node (ref "U1") (pin "P$7") (pinfunction "EECLK_P$7") (pintype "bidirectional"))
    )
    (net (code "235") (name "unconnected-(U1-EEDATA{slash}~{GANGED}-PadP$8)") (class "Default")
      (node (ref "U1") (pin "P$8") (pinfunction "EEDATA/~{GANGED}_P$8") (pintype "bidirectional"))
    )
    (net (code "236") (name "unconnected-(U1-GND-PadP$5)") (class "Default")
      (node (ref "U1") (pin "P$5") (pinfunction "GND_P$5") (pintype "bidirectional"))
    )
    (net (code "237") (name "unconnected-(U1-GND-PadP$24)") (class "Default")
      (node (ref "U1") (pin "P$24") (pinfunction "GND_P$24") (pintype "bidirectional"))
    )
    (net (code "238") (name "unconnected-(U1-GND-PadP$43)") (class "Default")
      (node (ref "U1") (pin "P$43") (pinfunction "GND_P$43") (pintype "bidirectional"))
    )
    (net (code "239") (name "unconnected-(U1-HUBCFG-PadP$40)") (class "Default")
      (node (ref "U1") (pin "P$40") (pinfunction "HUBCFG_P$40") (pintype "bidirectional"))
    )
    (net (code "240") (name "unconnected-(U1-MODE-PadP$48)") (class "Default")
      (node (ref "U1") (pin "P$48") (pinfunction "MODE_P$48") (pintype "bidirectional"))
    )
    (net (code "241") (name "unconnected-(U1-PORTDIS-PadP$42)") (class "Default")
      (node (ref "U1") (pin "P$42") (pinfunction "PORTDIS_P$42") (pintype "bidirectional"))
    )
    (net (code "242") (name "unconnected-(U1-PORTPWR-PadP$41)") (class "Default")
      (node (ref "U1") (pin "P$41") (pinfunction "PORTPWR_P$41") (pintype "bidirectional"))
    )
    (net (code "243") (name "unconnected-(U1-SUSPND-PadP$1)") (class "Default")
      (node (ref "U1") (pin "P$1") (pinfunction "SUSPND_P$1") (pintype "bidirectional"))
    )
    (net (code "244") (name "unconnected-(U1-VCC-PadP$9)") (class "Default")
      (node (ref "U1") (pin "P$9") (pinfunction "VCC_P$9") (pintype "bidirectional"))
    )
    (net (code "245") (name "unconnected-(U1-VCC-PadP$46)") (class "Default")
      (node (ref "U1") (pin "P$46") (pinfunction "VCC_P$46") (pintype "bidirectional"))
    )
    (net (code "246") (name "unconnected-(U1-XTAL1{slash}CLK48-PadP$45)") (class "Default")
      (node (ref "U1") (pin "P$45") (pinfunction "XTAL1/CLK48_P$45") (pintype "bidirectional"))
    )
    (net (code "247") (name "unconnected-(U1-XTAL2-PadP$44)") (class "Default")
      (node (ref "U1") (pin "P$44") (pinfunction "XTAL2_P$44") (pintype "bidirectional"))
    )
    (net (code "248") (name "unconnected-(U1-~{BUSPWR}-PadP$10)") (class "Default")
      (node (ref "U1") (pin "P$10") (pinfunction "~{BUSPWR}_P$10") (pintype "bidirectional"))
    )
    (net (code "249") (name "unconnected-(U1-~{EXTMEM}-PadP$47)") (class "Default")
      (node (ref "U1") (pin "P$47") (pinfunction "~{EXTMEM}_P$47") (pintype "bidirectional"))
    )
    (net (code "250") (name "unconnected-(U1-~{OVERCUR1}-PadP$12)") (class "Default")
      (node (ref "U1") (pin "P$12") (pinfunction "~{OVERCUR1}_P$12") (pintype "bidirectional"))
    )
    (net (code "251") (name "unconnected-(U1-~{OVERCUR2}-PadP$16)") (class "Default")
      (node (ref "U1") (pin "P$16") (pinfunction "~{OVERCUR2}_P$16") (pintype "bidirectional"))
    )
    (net (code "252") (name "unconnected-(U1-~{OVERCUR3}-PadP$20)") (class "Default")
      (node (ref "U1") (pin "P$20") (pinfunction "~{OVERCUR3}_P$20") (pintype "bidirectional"))
    )
    (net (code "253") (name "unconnected-(U1-~{OVERCUR4}-PadP$25)") (class "Default")
      (node (ref "U1") (pin "P$25") (pinfunction "~{OVERCUR4}_P$25") (pintype "bidirectional"))
    )
    (net (code "254") (name "unconnected-(U1-~{OVERCUR5}-PadP$29)") (class "Default")
      (node (ref "U1") (pin "P$29") (pinfunction "~{OVERCUR5}_P$29") (pintype "bidirectional"))
    )
    (net (code "255") (name "unconnected-(U1-~{OVERCUR6}-PadP$33)") (class "Default")
      (node (ref "U1") (pin "P$33") (pinfunction "~{OVERCUR6}_P$33") (pintype "bidirectional"))
    )
    (net (code "256") (name "unconnected-(U1-~{OVERCUR7}-PadP$37)") (class "Default")
      (node (ref "U1") (pin "P$37") (pinfunction "~{OVERCUR7}_P$37") (pintype "bidirectional"))
    )
    (net (code "257") (name "unconnected-(U1-~{PWRON1}-PadP$11)") (class "Default")
      (node (ref "U1") (pin "P$11") (pinfunction "~{PWRON1}_P$11") (pintype "bidirectional"))
    )
    (net (code "258") (name "unconnected-(U1-~{PWRON2}-PadP$15)") (class "Default")
      (node (ref "U1") (pin "P$15") (pinfunction "~{PWRON2}_P$15") (pintype "bidirectional"))
    )
    (net (code "259") (name "unconnected-(U1-~{PWRON3}-PadP$19)") (class "Default")
      (node (ref "U1") (pin "P$19") (pinfunction "~{PWRON3}_P$19") (pintype "bidirectional"))
    )
    (net (code "260") (name "unconnected-(U1-~{PWRON4}-PadP$23)") (class "Default")
      (node (ref "U1") (pin "P$23") (pinfunction "~{PWRON4}_P$23") (pintype "bidirectional"))
    )
    (net (code "261") (name "unconnected-(U1-~{PWRON5}-PadP$28)") (class "Default")
      (node (ref "U1") (pin "P$28") (pinfunction "~{PWRON5}_P$28") (pintype "bidirectional"))
    )
    (net (code "262") (name "unconnected-(U1-~{PWRON6}-PadP$32)") (class "Default")
      (node (ref "U1") (pin "P$32") (pinfunction "~{PWRON6}_P$32") (pintype "bidirectional"))
    )
    (net (code "263") (name "unconnected-(U1-~{PWRON7}-PadP$36)") (class "Default")
      (node (ref "U1") (pin "P$36") (pinfunction "~{PWRON7}_P$36") (pintype "bidirectional"))
    )
    (net (code "264") (name "unconnected-(U1-~{RESET}-PadP$6)") (class "Default")
      (node (ref "U1") (pin "P$6") (pinfunction "~{RESET}_P$6") (pintype "bidirectional"))
    )
  )
)
